# 16x16.net
KiCad netlist of a schematic drawn in EAGLE
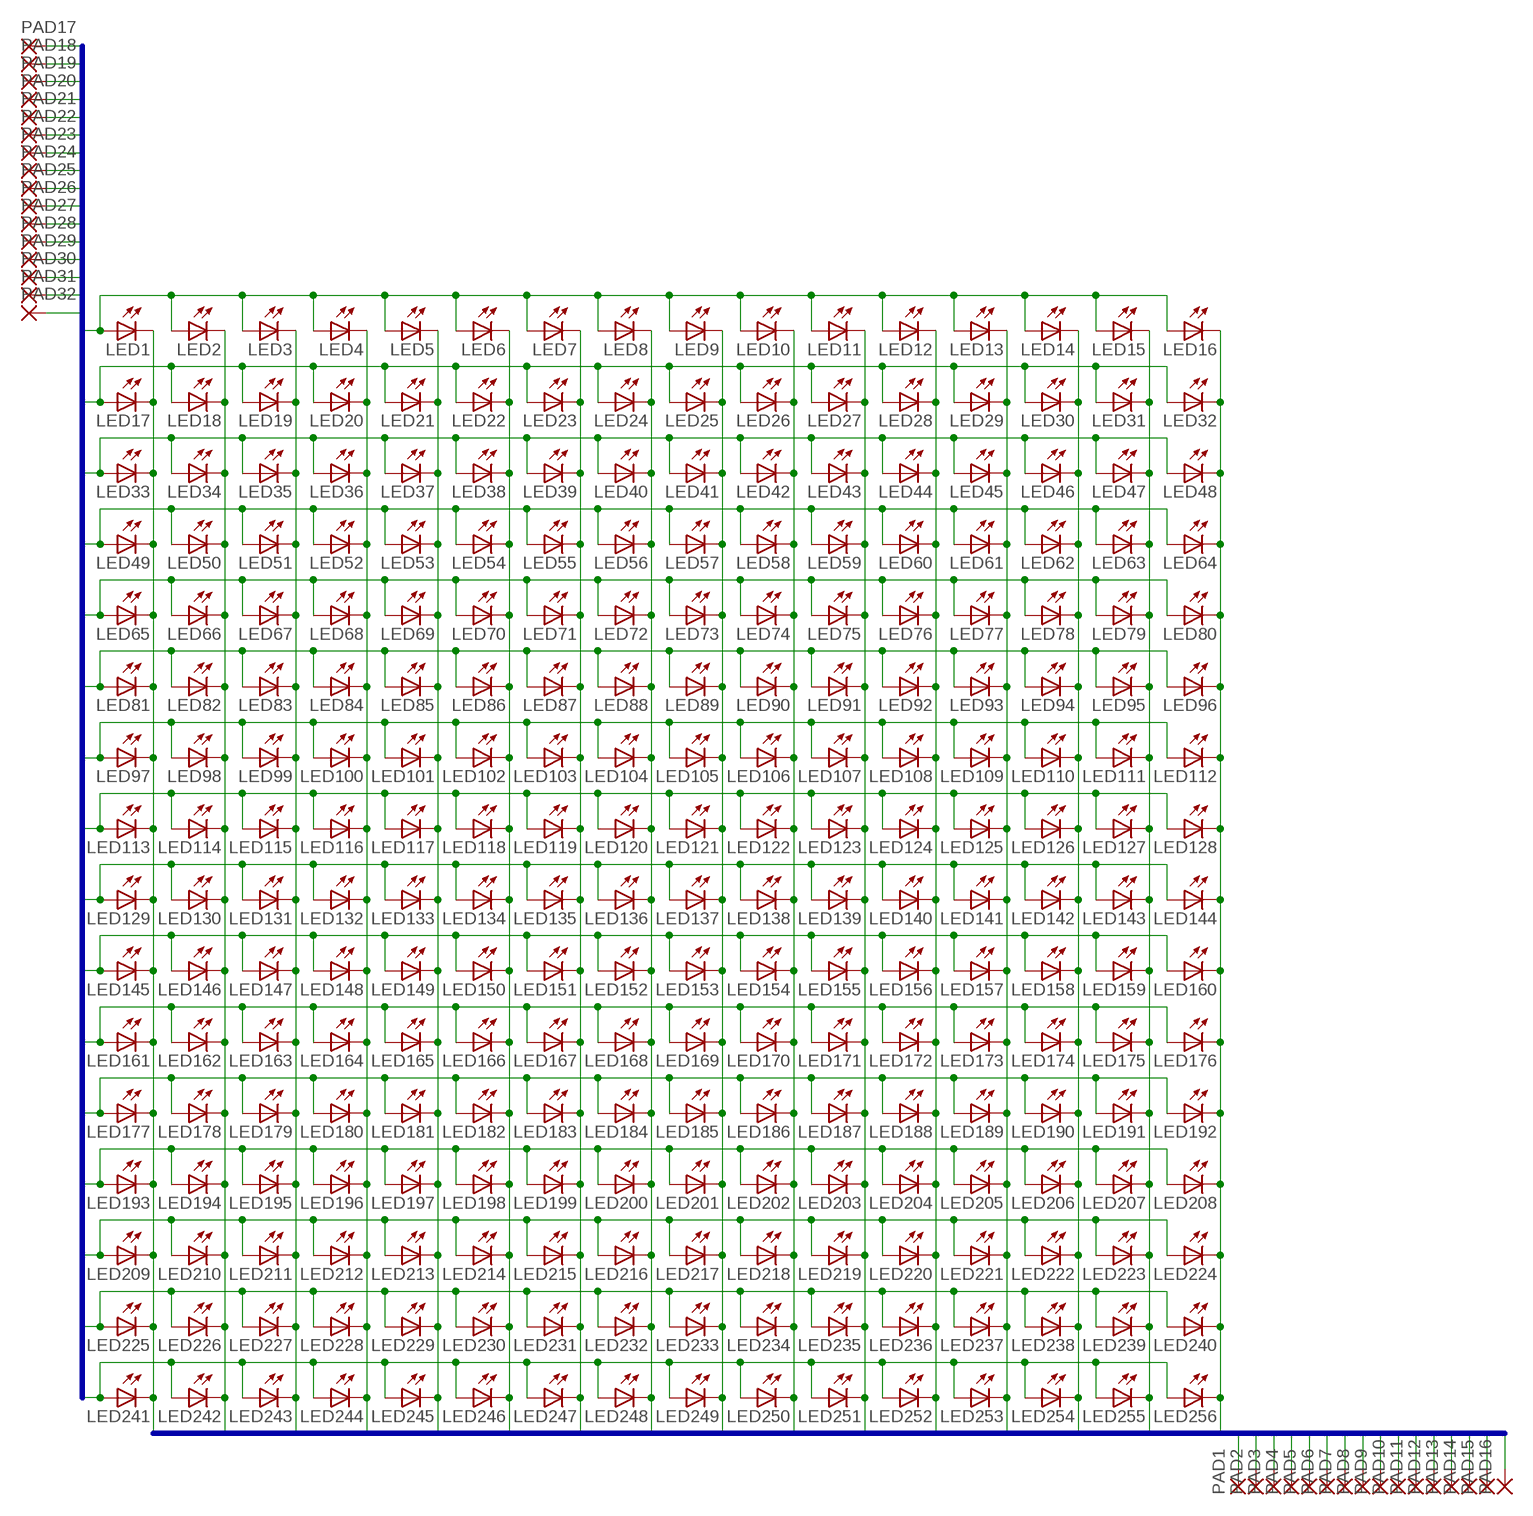
[diagram p0: schematic, sheet 1]

(export (version "E")
  (design (tool "Eeschema 10.0.6"))
  (components
    (comp (ref "LED1")
      (value "LEDSML0603")
      (footprint "eagle-import:SML0603")
      (libsource (lib "eagle-import") (part "LEDSML0603"))
    )
    (comp (ref "LED2")
      (value "LEDSML0603")
      (footprint "eagle-import:SML0603")
      (libsource (lib "eagle-import") (part "LEDSML0603"))
    )
    (comp (ref "LED3")
      (value "LEDSML0603")
      (footprint "eagle-import:SML0603")
      (libsource (lib "eagle-import") (part "LEDSML0603"))
    )
    (comp (ref "LED4")
      (value "LEDSML0603")
      (footprint "eagle-import:SML0603")
      (libsource (lib "eagle-import") (part "LEDSML0603"))
    )
    (comp (ref "LED5")
      (value "LEDSML0603")
      (footprint "eagle-import:SML0603")
      (libsource (lib "eagle-import") (part "LEDSML0603"))
    )
    (comp (ref "LED6")
      (value "LEDSML0603")
      (footprint "eagle-import:SML0603")
      (libsource (lib "eagle-import") (part "LEDSML0603"))
    )
    (comp (ref "LED7")
      (value "LEDSML0603")
      (footprint "eagle-import:SML0603")
      (libsource (lib "eagle-import") (part "LEDSML0603"))
    )
    (comp (ref "LED8")
      (value "LEDSML0603")
      (footprint "eagle-import:SML0603")
      (libsource (lib "eagle-import") (part "LEDSML0603"))
    )
    (comp (ref "LED9")
      (value "LEDSML0603")
      (footprint "eagle-import:SML0603")
      (libsource (lib "eagle-import") (part "LEDSML0603"))
    )
    (comp (ref "LED10")
      (value "LEDSML0603")
      (footprint "eagle-import:SML0603")
      (libsource (lib "eagle-import") (part "LEDSML0603"))
    )
    (comp (ref "LED11")
      (value "LEDSML0603")
      (footprint "eagle-import:SML0603")
      (libsource (lib "eagle-import") (part "LEDSML0603"))
    )
    (comp (ref "LED12")
      (value "LEDSML0603")
      (footprint "eagle-import:SML0603")
      (libsource (lib "eagle-import") (part "LEDSML0603"))
    )
    (comp (ref "LED13")
      (value "LEDSML0603")
      (footprint "eagle-import:SML0603")
      (libsource (lib "eagle-import") (part "LEDSML0603"))
    )
    (comp (ref "LED14")
      (value "LEDSML0603")
      (footprint "eagle-import:SML0603")
      (libsource (lib "eagle-import") (part "LEDSML0603"))
    )
    (comp (ref "LED15")
      (value "LEDSML0603")
      (footprint "eagle-import:SML0603")
      (libsource (lib "eagle-import") (part "LEDSML0603"))
    )
    (comp (ref "LED16")
      (value "LEDSML0603")
      (footprint "eagle-import:SML0603")
      (libsource (lib "eagle-import") (part "LEDSML0603"))
    )
    (comp (ref "LED17")
      (value "LEDSML0603")
      (footprint "eagle-import:SML0603")
      (libsource (lib "eagle-import") (part "LEDSML0603"))
    )
    (comp (ref "LED18")
      (value "LEDSML0603")
      (footprint "eagle-import:SML0603")
      (libsource (lib "eagle-import") (part "LEDSML0603"))
    )
    (comp (ref "LED19")
      (value "LEDSML0603")
      (footprint "eagle-import:SML0603")
      (libsource (lib "eagle-import") (part "LEDSML0603"))
    )
    (comp (ref "LED20")
      (value "LEDSML0603")
      (footprint "eagle-import:SML0603")
      (libsource (lib "eagle-import") (part "LEDSML0603"))
    )
    (comp (ref "LED21")
      (value "LEDSML0603")
      (footprint "eagle-import:SML0603")
      (libsource (lib "eagle-import") (part "LEDSML0603"))
    )
    (comp (ref "LED22")
      (value "LEDSML0603")
      (footprint "eagle-import:SML0603")
      (libsource (lib "eagle-import") (part "LEDSML0603"))
    )
    (comp (ref "LED23")
      (value "LEDSML0603")
      (footprint "eagle-import:SML0603")
      (libsource (lib "eagle-import") (part "LEDSML0603"))
    )
    (comp (ref "LED24")
      (value "LEDSML0603")
      (footprint "eagle-import:SML0603")
      (libsource (lib "eagle-import") (part "LEDSML0603"))
    )
    (comp (ref "LED25")
      (value "LEDSML0603")
      (footprint "eagle-import:SML0603")
      (libsource (lib "eagle-import") (part "LEDSML0603"))
    )
    (comp (ref "LED26")
      (value "LEDSML0603")
      (footprint "eagle-import:SML0603")
      (libsource (lib "eagle-import") (part "LEDSML0603"))
    )
    (comp (ref "LED27")
      (value "LEDSML0603")
      (footprint "eagle-import:SML0603")
      (libsource (lib "eagle-import") (part "LEDSML0603"))
    )
    (comp (ref "LED28")
      (value "LEDSML0603")
      (footprint "eagle-import:SML0603")
      (libsource (lib "eagle-import") (part "LEDSML0603"))
    )
    (comp (ref "LED29")
      (value "LEDSML0603")
      (footprint "eagle-import:SML0603")
      (libsource (lib "eagle-import") (part "LEDSML0603"))
    )
    (comp (ref "LED30")
      (value "LEDSML0603")
      (footprint "eagle-import:SML0603")
      (libsource (lib "eagle-import") (part "LEDSML0603"))
    )
    (comp (ref "LED31")
      (value "LEDSML0603")
      (footprint "eagle-import:SML0603")
      (libsource (lib "eagle-import") (part "LEDSML0603"))
    )
    (comp (ref "LED32")
      (value "LEDSML0603")
      (footprint "eagle-import:SML0603")
      (libsource (lib "eagle-import") (part "LEDSML0603"))
    )
    (comp (ref "LED33")
      (value "LEDSML0603")
      (footprint "eagle-import:SML0603")
      (libsource (lib "eagle-import") (part "LEDSML0603"))
    )
    (comp (ref "LED34")
      (value "LEDSML0603")
      (footprint "eagle-import:SML0603")
      (libsource (lib "eagle-import") (part "LEDSML0603"))
    )
    (comp (ref "LED35")
      (value "LEDSML0603")
      (footprint "eagle-import:SML0603")
      (libsource (lib "eagle-import") (part "LEDSML0603"))
    )
    (comp (ref "LED36")
      (value "LEDSML0603")
      (footprint "eagle-import:SML0603")
      (libsource (lib "eagle-import") (part "LEDSML0603"))
    )
    (comp (ref "LED37")
      (value "LEDSML0603")
      (footprint "eagle-import:SML0603")
      (libsource (lib "eagle-import") (part "LEDSML0603"))
    )
    (comp (ref "LED38")
      (value "LEDSML0603")
      (footprint "eagle-import:SML0603")
      (libsource (lib "eagle-import") (part "LEDSML0603"))
    )
    (comp (ref "LED39")
      (value "LEDSML0603")
      (footprint "eagle-import:SML0603")
      (libsource (lib "eagle-import") (part "LEDSML0603"))
    )
    (comp (ref "LED40")
      (value "LEDSML0603")
      (footprint "eagle-import:SML0603")
      (libsource (lib "eagle-import") (part "LEDSML0603"))
    )
    (comp (ref "LED41")
      (value "LEDSML0603")
      (footprint "eagle-import:SML0603")
      (libsource (lib "eagle-import") (part "LEDSML0603"))
    )
    (comp (ref "LED42")
      (value "LEDSML0603")
      (footprint "eagle-import:SML0603")
      (libsource (lib "eagle-import") (part "LEDSML0603"))
    )
    (comp (ref "LED43")
      (value "LEDSML0603")
      (footprint "eagle-import:SML0603")
      (libsource (lib "eagle-import") (part "LEDSML0603"))
    )
    (comp (ref "LED44")
      (value "LEDSML0603")
      (footprint "eagle-import:SML0603")
      (libsource (lib "eagle-import") (part "LEDSML0603"))
    )
    (comp (ref "LED45")
      (value "LEDSML0603")
      (footprint "eagle-import:SML0603")
      (libsource (lib "eagle-import") (part "LEDSML0603"))
    )
    (comp (ref "LED46")
      (value "LEDSML0603")
      (footprint "eagle-import:SML0603")
      (libsource (lib "eagle-import") (part "LEDSML0603"))
    )
    (comp (ref "LED47")
      (value "LEDSML0603")
      (footprint "eagle-import:SML0603")
      (libsource (lib "eagle-import") (part "LEDSML0603"))
    )
    (comp (ref "LED48")
      (value "LEDSML0603")
      (footprint "eagle-import:SML0603")
      (libsource (lib "eagle-import") (part "LEDSML0603"))
    )
    (comp (ref "LED49")
      (value "LEDSML0603")
      (footprint "eagle-import:SML0603")
      (libsource (lib "eagle-import") (part "LEDSML0603"))
    )
    (comp (ref "LED50")
      (value "LEDSML0603")
      (footprint "eagle-import:SML0603")
      (libsource (lib "eagle-import") (part "LEDSML0603"))
    )
    (comp (ref "LED51")
      (value "LEDSML0603")
      (footprint "eagle-import:SML0603")
      (libsource (lib "eagle-import") (part "LEDSML0603"))
    )
    (comp (ref "LED52")
      (value "LEDSML0603")
      (footprint "eagle-import:SML0603")
      (libsource (lib "eagle-import") (part "LEDSML0603"))
    )
    (comp (ref "LED53")
      (value "LEDSML0603")
      (footprint "eagle-import:SML0603")
      (libsource (lib "eagle-import") (part "LEDSML0603"))
    )
    (comp (ref "LED54")
      (value "LEDSML0603")
      (footprint "eagle-import:SML0603")
      (libsource (lib "eagle-import") (part "LEDSML0603"))
    )
    (comp (ref "LED55")
      (value "LEDSML0603")
      (footprint "eagle-import:SML0603")
      (libsource (lib "eagle-import") (part "LEDSML0603"))
    )
    (comp (ref "LED56")
      (value "LEDSML0603")
      (footprint "eagle-import:SML0603")
      (libsource (lib "eagle-import") (part "LEDSML0603"))
    )
    (comp (ref "LED57")
      (value "LEDSML0603")
      (footprint "eagle-import:SML0603")
      (libsource (lib "eagle-import") (part "LEDSML0603"))
    )
    (comp (ref "LED58")
      (value "LEDSML0603")
      (footprint "eagle-import:SML0603")
      (libsource (lib "eagle-import") (part "LEDSML0603"))
    )
    (comp (ref "LED59")
      (value "LEDSML0603")
      (footprint "eagle-import:SML0603")
      (libsource (lib "eagle-import") (part "LEDSML0603"))
    )
    (comp (ref "LED60")
      (value "LEDSML0603")
      (footprint "eagle-import:SML0603")
      (libsource (lib "eagle-import") (part "LEDSML0603"))
    )
    (comp (ref "LED61")
      (value "LEDSML0603")
      (footprint "eagle-import:SML0603")
      (libsource (lib "eagle-import") (part "LEDSML0603"))
    )
    (comp (ref "LED62")
      (value "LEDSML0603")
      (footprint "eagle-import:SML0603")
      (libsource (lib "eagle-import") (part "LEDSML0603"))
    )
    (comp (ref "LED63")
      (value "LEDSML0603")
      (footprint "eagle-import:SML0603")
      (libsource (lib "eagle-import") (part "LEDSML0603"))
    )
    (comp (ref "LED64")
      (value "LEDSML0603")
      (footprint "eagle-import:SML0603")
      (libsource (lib "eagle-import") (part "LEDSML0603"))
    )
    (comp (ref "LED65")
      (value "LEDSML0603")
      (footprint "eagle-import:SML0603")
      (libsource (lib "eagle-import") (part "LEDSML0603"))
    )
    (comp (ref "LED66")
      (value "LEDSML0603")
      (footprint "eagle-import:SML0603")
      (libsource (lib "eagle-import") (part "LEDSML0603"))
    )
    (comp (ref "LED67")
      (value "LEDSML0603")
      (footprint "eagle-import:SML0603")
      (libsource (lib "eagle-import") (part "LEDSML0603"))
    )
    (comp (ref "LED68")
      (value "LEDSML0603")
      (footprint "eagle-import:SML0603")
      (libsource (lib "eagle-import") (part "LEDSML0603"))
    )
    (comp (ref "LED69")
      (value "LEDSML0603")
      (footprint "eagle-import:SML0603")
      (libsource (lib "eagle-import") (part "LEDSML0603"))
    )
    (comp (ref "LED70")
      (value "LEDSML0603")
      (footprint "eagle-import:SML0603")
      (libsource (lib "eagle-import") (part "LEDSML0603"))
    )
    (comp (ref "LED71")
      (value "LEDSML0603")
      (footprint "eagle-import:SML0603")
      (libsource (lib "eagle-import") (part "LEDSML0603"))
    )
    (comp (ref "LED72")
      (value "LEDSML0603")
      (footprint "eagle-import:SML0603")
      (libsource (lib "eagle-import") (part "LEDSML0603"))
    )
    (comp (ref "LED73")
      (value "LEDSML0603")
      (footprint "eagle-import:SML0603")
      (libsource (lib "eagle-import") (part "LEDSML0603"))
    )
    (comp (ref "LED74")
      (value "LEDSML0603")
      (footprint "eagle-import:SML0603")
      (libsource (lib "eagle-import") (part "LEDSML0603"))
    )
    (comp (ref "LED75")
      (value "LEDSML0603")
      (footprint "eagle-import:SML0603")
      (libsource (lib "eagle-import") (part "LEDSML0603"))
    )
    (comp (ref "LED76")
      (value "LEDSML0603")
      (footprint "eagle-import:SML0603")
      (libsource (lib "eagle-import") (part "LEDSML0603"))
    )
    (comp (ref "LED77")
      (value "LEDSML0603")
      (footprint "eagle-import:SML0603")
      (libsource (lib "eagle-import") (part "LEDSML0603"))
    )
    (comp (ref "LED78")
      (value "LEDSML0603")
      (footprint "eagle-import:SML0603")
      (libsource (lib "eagle-import") (part "LEDSML0603"))
    )
    (comp (ref "LED79")
      (value "LEDSML0603")
      (footprint "eagle-import:SML0603")
      (libsource (lib "eagle-import") (part "LEDSML0603"))
    )
    (comp (ref "LED80")
      (value "LEDSML0603")
      (footprint "eagle-import:SML0603")
      (libsource (lib "eagle-import") (part "LEDSML0603"))
    )
    (comp (ref "LED81")
      (value "LEDSML0603")
      (footprint "eagle-import:SML0603")
      (libsource (lib "eagle-import") (part "LEDSML0603"))
    )
    (comp (ref "LED82")
      (value "LEDSML0603")
      (footprint "eagle-import:SML0603")
      (libsource (lib "eagle-import") (part "LEDSML0603"))
    )
    (comp (ref "LED83")
      (value "LEDSML0603")
      (footprint "eagle-import:SML0603")
      (libsource (lib "eagle-import") (part "LEDSML0603"))
    )
    (comp (ref "LED84")
      (value "LEDSML0603")
      (footprint "eagle-import:SML0603")
      (libsource (lib "eagle-import") (part "LEDSML0603"))
    )
    (comp (ref "LED85")
      (value "LEDSML0603")
      (footprint "eagle-import:SML0603")
      (libsource (lib "eagle-import") (part "LEDSML0603"))
    )
    (comp (ref "LED86")
      (value "LEDSML0603")
      (footprint "eagle-import:SML0603")
      (libsource (lib "eagle-import") (part "LEDSML0603"))
    )
    (comp (ref "LED87")
      (value "LEDSML0603")
      (footprint "eagle-import:SML0603")
      (libsource (lib "eagle-import") (part "LEDSML0603"))
    )
    (comp (ref "LED88")
      (value "LEDSML0603")
      (footprint "eagle-import:SML0603")
      (libsource (lib "eagle-import") (part "LEDSML0603"))
    )
    (comp (ref "LED89")
      (value "LEDSML0603")
      (footprint "eagle-import:SML0603")
      (libsource (lib "eagle-import") (part "LEDSML0603"))
    )
    (comp (ref "LED90")
      (value "LEDSML0603")
      (footprint "eagle-import:SML0603")
      (libsource (lib "eagle-import") (part "LEDSML0603"))
    )
    (comp (ref "LED91")
      (value "LEDSML0603")
      (footprint "eagle-import:SML0603")
      (libsource (lib "eagle-import") (part "LEDSML0603"))
    )
    (comp (ref "LED92")
      (value "LEDSML0603")
      (footprint "eagle-import:SML0603")
      (libsource (lib "eagle-import") (part "LEDSML0603"))
    )
    (comp (ref "LED93")
      (value "LEDSML0603")
      (footprint "eagle-import:SML0603")
      (libsource (lib "eagle-import") (part "LEDSML0603"))
    )
    (comp (ref "LED94")
      (value "LEDSML0603")
      (footprint "eagle-import:SML0603")
      (libsource (lib "eagle-import") (part "LEDSML0603"))
    )
    (comp (ref "LED95")
      (value "LEDSML0603")
      (footprint "eagle-import:SML0603")
      (libsource (lib "eagle-import") (part "LEDSML0603"))
    )
    (comp (ref "LED96")
      (value "LEDSML0603")
      (footprint "eagle-import:SML0603")
      (libsource (lib "eagle-import") (part "LEDSML0603"))
    )
    (comp (ref "LED97")
      (value "LEDSML0603")
      (footprint "eagle-import:SML0603")
      (libsource (lib "eagle-import") (part "LEDSML0603"))
    )
    (comp (ref "LED98")
      (value "LEDSML0603")
      (footprint "eagle-import:SML0603")
      (libsource (lib "eagle-import") (part "LEDSML0603"))
    )
    (comp (ref "LED99")
      (value "LEDSML0603")
      (footprint "eagle-import:SML0603")
      (libsource (lib "eagle-import") (part "LEDSML0603"))
    )
    (comp (ref "LED100")
      (value "LEDSML0603")
      (footprint "eagle-import:SML0603")
      (libsource (lib "eagle-import") (part "LEDSML0603"))
    )
    (comp (ref "LED101")
      (value "LEDSML0603")
      (footprint "eagle-import:SML0603")
      (libsource (lib "eagle-import") (part "LEDSML0603"))
    )
    (comp (ref "LED102")
      (value "LEDSML0603")
      (footprint "eagle-import:SML0603")
      (libsource (lib "eagle-import") (part "LEDSML0603"))
    )
    (comp (ref "LED103")
      (value "LEDSML0603")
      (footprint "eagle-import:SML0603")
      (libsource (lib "eagle-import") (part "LEDSML0603"))
    )
    (comp (ref "LED104")
      (value "LEDSML0603")
      (footprint "eagle-import:SML0603")
      (libsource (lib "eagle-import") (part "LEDSML0603"))
    )
    (comp (ref "LED105")
      (value "LEDSML0603")
      (footprint "eagle-import:SML0603")
      (libsource (lib "eagle-import") (part "LEDSML0603"))
    )
    (comp (ref "LED106")
      (value "LEDSML0603")
      (footprint "eagle-import:SML0603")
      (libsource (lib "eagle-import") (part "LEDSML0603"))
    )
    (comp (ref "LED107")
      (value "LEDSML0603")
      (footprint "eagle-import:SML0603")
      (libsource (lib "eagle-import") (part "LEDSML0603"))
    )
    (comp (ref "LED108")
      (value "LEDSML0603")
      (footprint "eagle-import:SML0603")
      (libsource (lib "eagle-import") (part "LEDSML0603"))
    )
    (comp (ref "LED109")
      (value "LEDSML0603")
      (footprint "eagle-import:SML0603")
      (libsource (lib "eagle-import") (part "LEDSML0603"))
    )
    (comp (ref "LED110")
      (value "LEDSML0603")
      (footprint "eagle-import:SML0603")
      (libsource (lib "eagle-import") (part "LEDSML0603"))
    )
    (comp (ref "LED111")
      (value "LEDSML0603")
      (footprint "eagle-import:SML0603")
      (libsource (lib "eagle-import") (part "LEDSML0603"))
    )
    (comp (ref "LED112")
      (value "LEDSML0603")
      (footprint "eagle-import:SML0603")
      (libsource (lib "eagle-import") (part "LEDSML0603"))
    )
    (comp (ref "LED113")
      (value "LEDSML0603")
      (footprint "eagle-import:SML0603")
      (libsource (lib "eagle-import") (part "LEDSML0603"))
    )
    (comp (ref "LED114")
      (value "LEDSML0603")
      (footprint "eagle-import:SML0603")
      (libsource (lib "eagle-import") (part "LEDSML0603"))
    )
    (comp (ref "LED115")
      (value "LEDSML0603")
      (footprint "eagle-import:SML0603")
      (libsource (lib "eagle-import") (part "LEDSML0603"))
    )
    (comp (ref "LED116")
      (value "LEDSML0603")
      (footprint "eagle-import:SML0603")
      (libsource (lib "eagle-import") (part "LEDSML0603"))
    )
    (comp (ref "LED117")
      (value "LEDSML0603")
      (footprint "eagle-import:SML0603")
      (libsource (lib "eagle-import") (part "LEDSML0603"))
    )
    (comp (ref "LED118")
      (value "LEDSML0603")
      (footprint "eagle-import:SML0603")
      (libsource (lib "eagle-import") (part "LEDSML0603"))
    )
    (comp (ref "LED119")
      (value "LEDSML0603")
      (footprint "eagle-import:SML0603")
      (libsource (lib "eagle-import") (part "LEDSML0603"))
    )
    (comp (ref "LED120")
      (value "LEDSML0603")
      (footprint "eagle-import:SML0603")
      (libsource (lib "eagle-import") (part "LEDSML0603"))
    )
    (comp (ref "LED121")
      (value "LEDSML0603")
      (footprint "eagle-import:SML0603")
      (libsource (lib "eagle-import") (part "LEDSML0603"))
    )
    (comp (ref "LED122")
      (value "LEDSML0603")
      (footprint "eagle-import:SML0603")
      (libsource (lib "eagle-import") (part "LEDSML0603"))
    )
    (comp (ref "LED123")
      (value "LEDSML0603")
      (footprint "eagle-import:SML0603")
      (libsource (lib "eagle-import") (part "LEDSML0603"))
    )
    (comp (ref "LED124")
      (value "LEDSML0603")
      (footprint "eagle-import:SML0603")
      (libsource (lib "eagle-import") (part "LEDSML0603"))
    )
    (comp (ref "LED125")
      (value "LEDSML0603")
      (footprint "eagle-import:SML0603")
      (libsource (lib "eagle-import") (part "LEDSML0603"))
    )
    (comp (ref "LED126")
      (value "LEDSML0603")
      (footprint "eagle-import:SML0603")
      (libsource (lib "eagle-import") (part "LEDSML0603"))
    )
    (comp (ref "LED127")
      (value "LEDSML0603")
      (footprint "eagle-import:SML0603")
      (libsource (lib "eagle-import") (part "LEDSML0603"))
    )
    (comp (ref "LED128")
      (value "LEDSML0603")
      (footprint "eagle-import:SML0603")
      (libsource (lib "eagle-import") (part "LEDSML0603"))
    )
    (comp (ref "LED129")
      (value "LEDSML0603")
      (footprint "eagle-import:SML0603")
      (libsource (lib "eagle-import") (part "LEDSML0603"))
    )
    (comp (ref "LED130")
      (value "LEDSML0603")
      (footprint "eagle-import:SML0603")
      (libsource (lib "eagle-import") (part "LEDSML0603"))
    )
    (comp (ref "LED131")
      (value "LEDSML0603")
      (footprint "eagle-import:SML0603")
      (libsource (lib "eagle-import") (part "LEDSML0603"))
    )
    (comp (ref "LED132")
      (value "LEDSML0603")
      (footprint "eagle-import:SML0603")
      (libsource (lib "eagle-import") (part "LEDSML0603"))
    )
    (comp (ref "LED133")
      (value "LEDSML0603")
      (footprint "eagle-import:SML0603")
      (libsource (lib "eagle-import") (part "LEDSML0603"))
    )
    (comp (ref "LED134")
      (value "LEDSML0603")
      (footprint "eagle-import:SML0603")
      (libsource (lib "eagle-import") (part "LEDSML0603"))
    )
    (comp (ref "LED135")
      (value "LEDSML0603")
      (footprint "eagle-import:SML0603")
      (libsource (lib "eagle-import") (part "LEDSML0603"))
    )
    (comp (ref "LED136")
      (value "LEDSML0603")
      (footprint "eagle-import:SML0603")
      (libsource (lib "eagle-import") (part "LEDSML0603"))
    )
    (comp (ref "LED137")
      (value "LEDSML0603")
      (footprint "eagle-import:SML0603")
      (libsource (lib "eagle-import") (part "LEDSML0603"))
    )
    (comp (ref "LED138")
      (value "LEDSML0603")
      (footprint "eagle-import:SML0603")
      (libsource (lib "eagle-import") (part "LEDSML0603"))
    )
    (comp (ref "LED139")
      (value "LEDSML0603")
      (footprint "eagle-import:SML0603")
      (libsource (lib "eagle-import") (part "LEDSML0603"))
    )
    (comp (ref "LED140")
      (value "LEDSML0603")
      (footprint "eagle-import:SML0603")
      (libsource (lib "eagle-import") (part "LEDSML0603"))
    )
    (comp (ref "LED141")
      (value "LEDSML0603")
      (footprint "eagle-import:SML0603")
      (libsource (lib "eagle-import") (part "LEDSML0603"))
    )
    (comp (ref "LED142")
      (value "LEDSML0603")
      (footprint "eagle-import:SML0603")
      (libsource (lib "eagle-import") (part "LEDSML0603"))
    )
    (comp (ref "LED143")
      (value "LEDSML0603")
      (footprint "eagle-import:SML0603")
      (libsource (lib "eagle-import") (part "LEDSML0603"))
    )
    (comp (ref "LED144")
      (value "LEDSML0603")
      (footprint "eagle-import:SML0603")
      (libsource (lib "eagle-import") (part "LEDSML0603"))
    )
    (comp (ref "LED145")
      (value "LEDSML0603")
      (footprint "eagle-import:SML0603")
      (libsource (lib "eagle-import") (part "LEDSML0603"))
    )
    (comp (ref "LED146")
      (value "LEDSML0603")
      (footprint "eagle-import:SML0603")
      (libsource (lib "eagle-import") (part "LEDSML0603"))
    )
    (comp (ref "LED147")
      (value "LEDSML0603")
      (footprint "eagle-import:SML0603")
      (libsource (lib "eagle-import") (part "LEDSML0603"))
    )
    (comp (ref "LED148")
      (value "LEDSML0603")
      (footprint "eagle-import:SML0603")
      (libsource (lib "eagle-import") (part "LEDSML0603"))
    )
    (comp (ref "LED149")
      (value "LEDSML0603")
      (footprint "eagle-import:SML0603")
      (libsource (lib "eagle-import") (part "LEDSML0603"))
    )
    (comp (ref "LED150")
      (value "LEDSML0603")
      (footprint "eagle-import:SML0603")
      (libsource (lib "eagle-import") (part "LEDSML0603"))
    )
    (comp (ref "LED151")
      (value "LEDSML0603")
      (footprint "eagle-import:SML0603")
      (libsource (lib "eagle-import") (part "LEDSML0603"))
    )
    (comp (ref "LED152")
      (value "LEDSML0603")
      (footprint "eagle-import:SML0603")
      (libsource (lib "eagle-import") (part "LEDSML0603"))
    )
    (comp (ref "LED153")
      (value "LEDSML0603")
      (footprint "eagle-import:SML0603")
      (libsource (lib "eagle-import") (part "LEDSML0603"))
    )
    (comp (ref "LED154")
      (value "LEDSML0603")
      (footprint "eagle-import:SML0603")
      (libsource (lib "eagle-import") (part "LEDSML0603"))
    )
    (comp (ref "LED155")
      (value "LEDSML0603")
      (footprint "eagle-import:SML0603")
      (libsource (lib "eagle-import") (part "LEDSML0603"))
    )
    (comp (ref "LED156")
      (value "LEDSML0603")
      (footprint "eagle-import:SML0603")
      (libsource (lib "eagle-import") (part "LEDSML0603"))
    )
    (comp (ref "LED157")
      (value "LEDSML0603")
      (footprint "eagle-import:SML0603")
      (libsource (lib "eagle-import") (part "LEDSML0603"))
    )
    (comp (ref "LED158")
      (value "LEDSML0603")
      (footprint "eagle-import:SML0603")
      (libsource (lib "eagle-import") (part "LEDSML0603"))
    )
    (comp (ref "LED159")
      (value "LEDSML0603")
      (footprint "eagle-import:SML0603")
      (libsource (lib "eagle-import") (part "LEDSML0603"))
    )
    (comp (ref "LED160")
      (value "LEDSML0603")
      (footprint "eagle-import:SML0603")
      (libsource (lib "eagle-import") (part "LEDSML0603"))
    )
    (comp (ref "LED161")
      (value "LEDSML0603")
      (footprint "eagle-import:SML0603")
      (libsource (lib "eagle-import") (part "LEDSML0603"))
    )
    (comp (ref "LED162")
      (value "LEDSML0603")
      (footprint "eagle-import:SML0603")
      (libsource (lib "eagle-import") (part "LEDSML0603"))
    )
    (comp (ref "LED163")
      (value "LEDSML0603")
      (footprint "eagle-import:SML0603")
      (libsource (lib "eagle-import") (part "LEDSML0603"))
    )
    (comp (ref "LED164")
      (value "LEDSML0603")
      (footprint "eagle-import:SML0603")
      (libsource (lib "eagle-import") (part "LEDSML0603"))
    )
    (comp (ref "LED165")
      (value "LEDSML0603")
      (footprint "eagle-import:SML0603")
      (libsource (lib "eagle-import") (part "LEDSML0603"))
    )
    (comp (ref "LED166")
      (value "LEDSML0603")
      (footprint "eagle-import:SML0603")
      (libsource (lib "eagle-import") (part "LEDSML0603"))
    )
    (comp (ref "LED167")
      (value "LEDSML0603")
      (footprint "eagle-import:SML0603")
      (libsource (lib "eagle-import") (part "LEDSML0603"))
    )
    (comp (ref "LED168")
      (value "LEDSML0603")
      (footprint "eagle-import:SML0603")
      (libsource (lib "eagle-import") (part "LEDSML0603"))
    )
    (comp (ref "LED169")
      (value "LEDSML0603")
      (footprint "eagle-import:SML0603")
      (libsource (lib "eagle-import") (part "LEDSML0603"))
    )
    (comp (ref "LED170")
      (value "LEDSML0603")
      (footprint "eagle-import:SML0603")
      (libsource (lib "eagle-import") (part "LEDSML0603"))
    )
    (comp (ref "LED171")
      (value "LEDSML0603")
      (footprint "eagle-import:SML0603")
      (libsource (lib "eagle-import") (part "LEDSML0603"))
    )
    (comp (ref "LED172")
      (value "LEDSML0603")
      (footprint "eagle-import:SML0603")
      (libsource (lib "eagle-import") (part "LEDSML0603"))
    )
    (comp (ref "LED173")
      (value "LEDSML0603")
      (footprint "eagle-import:SML0603")
      (libsource (lib "eagle-import") (part "LEDSML0603"))
    )
    (comp (ref "LED174")
      (value "LEDSML0603")
      (footprint "eagle-import:SML0603")
      (libsource (lib "eagle-import") (part "LEDSML0603"))
    )
    (comp (ref "LED175")
      (value "LEDSML0603")
      (footprint "eagle-import:SML0603")
      (libsource (lib "eagle-import") (part "LEDSML0603"))
    )
    (comp (ref "LED176")
      (value "LEDSML0603")
      (footprint "eagle-import:SML0603")
      (libsource (lib "eagle-import") (part "LEDSML0603"))
    )
    (comp (ref "LED177")
      (value "LEDSML0603")
      (footprint "eagle-import:SML0603")
      (libsource (lib "eagle-import") (part "LEDSML0603"))
    )
    (comp (ref "LED178")
      (value "LEDSML0603")
      (footprint "eagle-import:SML0603")
      (libsource (lib "eagle-import") (part "LEDSML0603"))
    )
    (comp (ref "LED179")
      (value "LEDSML0603")
      (footprint "eagle-import:SML0603")
      (libsource (lib "eagle-import") (part "LEDSML0603"))
    )
    (comp (ref "LED180")
      (value "LEDSML0603")
      (footprint "eagle-import:SML0603")
      (libsource (lib "eagle-import") (part "LEDSML0603"))
    )
    (comp (ref "LED181")
      (value "LEDSML0603")
      (footprint "eagle-import:SML0603")
      (libsource (lib "eagle-import") (part "LEDSML0603"))
    )
    (comp (ref "LED182")
      (value "LEDSML0603")
      (footprint "eagle-import:SML0603")
      (libsource (lib "eagle-import") (part "LEDSML0603"))
    )
    (comp (ref "LED183")
      (value "LEDSML0603")
      (footprint "eagle-import:SML0603")
      (libsource (lib "eagle-import") (part "LEDSML0603"))
    )
    (comp (ref "LED184")
      (value "LEDSML0603")
      (footprint "eagle-import:SML0603")
      (libsource (lib "eagle-import") (part "LEDSML0603"))
    )
    (comp (ref "LED185")
      (value "LEDSML0603")
      (footprint "eagle-import:SML0603")
      (libsource (lib "eagle-import") (part "LEDSML0603"))
    )
    (comp (ref "LED186")
      (value "LEDSML0603")
      (footprint "eagle-import:SML0603")
      (libsource (lib "eagle-import") (part "LEDSML0603"))
    )
    (comp (ref "LED187")
      (value "LEDSML0603")
      (footprint "eagle-import:SML0603")
      (libsource (lib "eagle-import") (part "LEDSML0603"))
    )
    (comp (ref "LED188")
      (value "LEDSML0603")
      (footprint "eagle-import:SML0603")
      (libsource (lib "eagle-import") (part "LEDSML0603"))
    )
    (comp (ref "LED189")
      (value "LEDSML0603")
      (footprint "eagle-import:SML0603")
      (libsource (lib "eagle-import") (part "LEDSML0603"))
    )
    (comp (ref "LED190")
      (value "LEDSML0603")
      (footprint "eagle-import:SML0603")
      (libsource (lib "eagle-import") (part "LEDSML0603"))
    )
    (comp (ref "LED191")
      (value "LEDSML0603")
      (footprint "eagle-import:SML0603")
      (libsource (lib "eagle-import") (part "LEDSML0603"))
    )
    (comp (ref "LED192")
      (value "LEDSML0603")
      (footprint "eagle-import:SML0603")
      (libsource (lib "eagle-import") (part "LEDSML0603"))
    )
    (comp (ref "LED193")
      (value "LEDSML0603")
      (footprint "eagle-import:SML0603")
      (libsource (lib "eagle-import") (part "LEDSML0603"))
    )
    (comp (ref "LED194")
      (value "LEDSML0603")
      (footprint "eagle-import:SML0603")
      (libsource (lib "eagle-import") (part "LEDSML0603"))
    )
    (comp (ref "LED195")
      (value "LEDSML0603")
      (footprint "eagle-import:SML0603")
      (libsource (lib "eagle-import") (part "LEDSML0603"))
    )
    (comp (ref "LED196")
      (value "LEDSML0603")
      (footprint "eagle-import:SML0603")
      (libsource (lib "eagle-import") (part "LEDSML0603"))
    )
    (comp (ref "LED197")
      (value "LEDSML0603")
      (footprint "eagle-import:SML0603")
      (libsource (lib "eagle-import") (part "LEDSML0603"))
    )
    (comp (ref "LED198")
      (value "LEDSML0603")
      (footprint "eagle-import:SML0603")
      (libsource (lib "eagle-import") (part "LEDSML0603"))
    )
    (comp (ref "LED199")
      (value "LEDSML0603")
      (footprint "eagle-import:SML0603")
      (libsource (lib "eagle-import") (part "LEDSML0603"))
    )
    (comp (ref "LED200")
      (value "LEDSML0603")
      (footprint "eagle-import:SML0603")
      (libsource (lib "eagle-import") (part "LEDSML0603"))
    )
    (comp (ref "LED201")
      (value "LEDSML0603")
      (footprint "eagle-import:SML0603")
      (libsource (lib "eagle-import") (part "LEDSML0603"))
    )
    (comp (ref "LED202")
      (value "LEDSML0603")
      (footprint "eagle-import:SML0603")
      (libsource (lib "eagle-import") (part "LEDSML0603"))
    )
    (comp (ref "LED203")
      (value "LEDSML0603")
      (footprint "eagle-import:SML0603")
      (libsource (lib "eagle-import") (part "LEDSML0603"))
    )
    (comp (ref "LED204")
      (value "LEDSML0603")
      (footprint "eagle-import:SML0603")
      (libsource (lib "eagle-import") (part "LEDSML0603"))
    )
    (comp (ref "LED205")
      (value "LEDSML0603")
      (footprint "eagle-import:SML0603")
      (libsource (lib "eagle-import") (part "LEDSML0603"))
    )
    (comp (ref "LED206")
      (value "LEDSML0603")
      (footprint "eagle-import:SML0603")
      (libsource (lib "eagle-import") (part "LEDSML0603"))
    )
    (comp (ref "LED207")
      (value "LEDSML0603")
      (footprint "eagle-import:SML0603")
      (libsource (lib "eagle-import") (part "LEDSML0603"))
    )
    (comp (ref "LED208")
      (value "LEDSML0603")
      (footprint "eagle-import:SML0603")
      (libsource (lib "eagle-import") (part "LEDSML0603"))
    )
    (comp (ref "LED209")
      (value "LEDSML0603")
      (footprint "eagle-import:SML0603")
      (libsource (lib "eagle-import") (part "LEDSML0603"))
    )
    (comp (ref "LED210")
      (value "LEDSML0603")
      (footprint "eagle-import:SML0603")
      (libsource (lib "eagle-import") (part "LEDSML0603"))
    )
    (comp (ref "LED211")
      (value "LEDSML0603")
      (footprint "eagle-import:SML0603")
      (libsource (lib "eagle-import") (part "LEDSML0603"))
    )
    (comp (ref "LED212")
      (value "LEDSML0603")
      (footprint "eagle-import:SML0603")
      (libsource (lib "eagle-import") (part "LEDSML0603"))
    )
    (comp (ref "LED213")
      (value "LEDSML0603")
      (footprint "eagle-import:SML0603")
      (libsource (lib "eagle-import") (part "LEDSML0603"))
    )
    (comp (ref "LED214")
      (value "LEDSML0603")
      (footprint "eagle-import:SML0603")
      (libsource (lib "eagle-import") (part "LEDSML0603"))
    )
    (comp (ref "LED215")
      (value "LEDSML0603")
      (footprint "eagle-import:SML0603")
      (libsource (lib "eagle-import") (part "LEDSML0603"))
    )
    (comp (ref "LED216")
      (value "LEDSML0603")
      (footprint "eagle-import:SML0603")
      (libsource (lib "eagle-import") (part "LEDSML0603"))
    )
    (comp (ref "LED217")
      (value "LEDSML0603")
      (footprint "eagle-import:SML0603")
      (libsource (lib "eagle-import") (part "LEDSML0603"))
    )
    (comp (ref "LED218")
      (value "LEDSML0603")
      (footprint "eagle-import:SML0603")
      (libsource (lib "eagle-import") (part "LEDSML0603"))
    )
    (comp (ref "LED219")
      (value "LEDSML0603")
      (footprint "eagle-import:SML0603")
      (libsource (lib "eagle-import") (part "LEDSML0603"))
    )
    (comp (ref "LED220")
      (value "LEDSML0603")
      (footprint "eagle-import:SML0603")
      (libsource (lib "eagle-import") (part "LEDSML0603"))
    )
    (comp (ref "LED221")
      (value "LEDSML0603")
      (footprint "eagle-import:SML0603")
      (libsource (lib "eagle-import") (part "LEDSML0603"))
    )
    (comp (ref "LED222")
      (value "LEDSML0603")
      (footprint "eagle-import:SML0603")
      (libsource (lib "eagle-import") (part "LEDSML0603"))
    )
    (comp (ref "LED223")
      (value "LEDSML0603")
      (footprint "eagle-import:SML0603")
      (libsource (lib "eagle-import") (part "LEDSML0603"))
    )
    (comp (ref "LED224")
      (value "LEDSML0603")
      (footprint "eagle-import:SML0603")
      (libsource (lib "eagle-import") (part "LEDSML0603"))
    )
    (comp (ref "LED225")
      (value "LEDSML0603")
      (footprint "eagle-import:SML0603")
      (libsource (lib "eagle-import") (part "LEDSML0603"))
    )
    (comp (ref "LED226")
      (value "LEDSML0603")
      (footprint "eagle-import:SML0603")
      (libsource (lib "eagle-import") (part "LEDSML0603"))
    )
    (comp (ref "LED227")
      (value "LEDSML0603")
      (footprint "eagle-import:SML0603")
      (libsource (lib "eagle-import") (part "LEDSML0603"))
    )
    (comp (ref "LED228")
      (value "LEDSML0603")
      (footprint "eagle-import:SML0603")
      (libsource (lib "eagle-import") (part "LEDSML0603"))
    )
    (comp (ref "LED229")
      (value "LEDSML0603")
      (footprint "eagle-import:SML0603")
      (libsource (lib "eagle-import") (part "LEDSML0603"))
    )
    (comp (ref "LED230")
      (value "LEDSML0603")
      (footprint "eagle-import:SML0603")
      (libsource (lib "eagle-import") (part "LEDSML0603"))
    )
    (comp (ref "LED231")
      (value "LEDSML0603")
      (footprint "eagle-import:SML0603")
      (libsource (lib "eagle-import") (part "LEDSML0603"))
    )
    (comp (ref "LED232")
      (value "LEDSML0603")
      (footprint "eagle-import:SML0603")
      (libsource (lib "eagle-import") (part "LEDSML0603"))
    )
    (comp (ref "LED233")
      (value "LEDSML0603")
      (footprint "eagle-import:SML0603")
      (libsource (lib "eagle-import") (part "LEDSML0603"))
    )
    (comp (ref "LED234")
      (value "LEDSML0603")
      (footprint "eagle-import:SML0603")
      (libsource (lib "eagle-import") (part "LEDSML0603"))
    )
    (comp (ref "LED235")
      (value "LEDSML0603")
      (footprint "eagle-import:SML0603")
      (libsource (lib "eagle-import") (part "LEDSML0603"))
    )
    (comp (ref "LED236")
      (value "LEDSML0603")
      (footprint "eagle-import:SML0603")
      (libsource (lib "eagle-import") (part "LEDSML0603"))
    )
    (comp (ref "LED237")
      (value "LEDSML0603")
      (footprint "eagle-import:SML0603")
      (libsource (lib "eagle-import") (part "LEDSML0603"))
    )
    (comp (ref "LED238")
      (value "LEDSML0603")
      (footprint "eagle-import:SML0603")
      (libsource (lib "eagle-import") (part "LEDSML0603"))
    )
    (comp (ref "LED239")
      (value "LEDSML0603")
      (footprint "eagle-import:SML0603")
      (libsource (lib "eagle-import") (part "LEDSML0603"))
    )
    (comp (ref "LED240")
      (value "LEDSML0603")
      (footprint "eagle-import:SML0603")
      (libsource (lib "eagle-import") (part "LEDSML0603"))
    )
    (comp (ref "LED241")
      (value "LEDSML0603")
      (footprint "eagle-import:SML0603")
      (libsource (lib "eagle-import") (part "LEDSML0603"))
    )
    (comp (ref "LED242")
      (value "LEDSML0603")
      (footprint "eagle-import:SML0603")
      (libsource (lib "eagle-import") (part "LEDSML0603"))
    )
    (comp (ref "LED243")
      (value "LEDSML0603")
      (footprint "eagle-import:SML0603")
      (libsource (lib "eagle-import") (part "LEDSML0603"))
    )
    (comp (ref "LED244")
      (value "LEDSML0603")
      (footprint "eagle-import:SML0603")
      (libsource (lib "eagle-import") (part "LEDSML0603"))
    )
    (comp (ref "LED245")
      (value "LEDSML0603")
      (footprint "eagle-import:SML0603")
      (libsource (lib "eagle-import") (part "LEDSML0603"))
    )
    (comp (ref "LED246")
      (value "LEDSML0603")
      (footprint "eagle-import:SML0603")
      (libsource (lib "eagle-import") (part "LEDSML0603"))
    )
    (comp (ref "LED247")
      (value "LEDSML0603")
      (footprint "eagle-import:SML0603")
      (libsource (lib "eagle-import") (part "LEDSML0603"))
    )
    (comp (ref "LED248")
      (value "LEDSML0603")
      (footprint "eagle-import:SML0603")
      (libsource (lib "eagle-import") (part "LEDSML0603"))
    )
    (comp (ref "LED249")
      (value "LEDSML0603")
      (footprint "eagle-import:SML0603")
      (libsource (lib "eagle-import") (part "LEDSML0603"))
    )
    (comp (ref "LED250")
      (value "LEDSML0603")
      (footprint "eagle-import:SML0603")
      (libsource (lib "eagle-import") (part "LEDSML0603"))
    )
    (comp (ref "LED251")
      (value "LEDSML0603")
      (footprint "eagle-import:SML0603")
      (libsource (lib "eagle-import") (part "LEDSML0603"))
    )
    (comp (ref "LED252")
      (value "LEDSML0603")
      (footprint "eagle-import:SML0603")
      (libsource (lib "eagle-import") (part "LEDSML0603"))
    )
    (comp (ref "LED253")
      (value "LEDSML0603")
      (footprint "eagle-import:SML0603")
      (libsource (lib "eagle-import") (part "LEDSML0603"))
    )
    (comp (ref "LED254")
      (value "LEDSML0603")
      (footprint "eagle-import:SML0603")
      (libsource (lib "eagle-import") (part "LEDSML0603"))
    )
    (comp (ref "LED255")
      (value "LEDSML0603")
      (footprint "eagle-import:SML0603")
      (libsource (lib "eagle-import") (part "LEDSML0603"))
    )
    (comp (ref "LED256")
      (value "LEDSML0603")
      (footprint "eagle-import:SML0603")
      (libsource (lib "eagle-import") (part "LEDSML0603"))
    )
    (comp (ref "PAD1")
      (value "SMD2")
      (footprint "eagle-import:SMD1,27-2,54")
      (libsource (lib "eagle-import") (part "SMD2"))
    )
    (comp (ref "PAD2")
      (value "SMD2")
      (footprint "eagle-import:SMD1,27-2,54")
      (libsource (lib "eagle-import") (part "SMD2"))
    )
    (comp (ref "PAD3")
      (value "SMD2")
      (footprint "eagle-import:SMD1,27-2,54")
      (libsource (lib "eagle-import") (part "SMD2"))
    )
    (comp (ref "PAD4")
      (value "SMD2")
      (footprint "eagle-import:SMD1,27-2,54")
      (libsource (lib "eagle-import") (part "SMD2"))
    )
    (comp (ref "PAD5")
      (value "SMD2")
      (footprint "eagle-import:SMD1,27-2,54")
      (libsource (lib "eagle-import") (part "SMD2"))
    )
    (comp (ref "PAD6")
      (value "SMD2")
      (footprint "eagle-import:SMD1,27-2,54")
      (libsource (lib "eagle-import") (part "SMD2"))
    )
    (comp (ref "PAD7")
      (value "SMD2")
      (footprint "eagle-import:SMD1,27-2,54")
      (libsource (lib "eagle-import") (part "SMD2"))
    )
    (comp (ref "PAD8")
      (value "SMD2")
      (footprint "eagle-import:SMD1,27-2,54")
      (libsource (lib "eagle-import") (part "SMD2"))
    )
    (comp (ref "PAD9")
      (value "SMD2")
      (footprint "eagle-import:SMD1,27-2,54")
      (libsource (lib "eagle-import") (part "SMD2"))
    )
    (comp (ref "PAD10")
      (value "SMD2")
      (footprint "eagle-import:SMD1,27-2,54")
      (libsource (lib "eagle-import") (part "SMD2"))
    )
    (comp (ref "PAD11")
      (value "SMD2")
      (footprint "eagle-import:SMD1,27-2,54")
      (libsource (lib "eagle-import") (part "SMD2"))
    )
    (comp (ref "PAD12")
      (value "SMD2")
      (footprint "eagle-import:SMD1,27-2,54")
      (libsource (lib "eagle-import") (part "SMD2"))
    )
    (comp (ref "PAD13")
      (value "SMD2")
      (footprint "eagle-import:SMD1,27-2,54")
      (libsource (lib "eagle-import") (part "SMD2"))
    )
    (comp (ref "PAD14")
      (value "SMD2")
      (footprint "eagle-import:SMD1,27-2,54")
      (libsource (lib "eagle-import") (part "SMD2"))
    )
    (comp (ref "PAD15")
      (value "SMD2")
      (footprint "eagle-import:SMD1,27-2,54")
      (libsource (lib "eagle-import") (part "SMD2"))
    )
    (comp (ref "PAD16")
      (value "SMD2")
      (footprint "eagle-import:SMD1,27-2,54")
      (libsource (lib "eagle-import") (part "SMD2"))
    )
    (comp (ref "PAD17")
      (value "SMD2")
      (footprint "eagle-import:SMD1,27-2,54")
      (libsource (lib "eagle-import") (part "SMD2"))
    )
    (comp (ref "PAD18")
      (value "SMD2")
      (footprint "eagle-import:SMD1,27-2,54")
      (libsource (lib "eagle-import") (part "SMD2"))
    )
    (comp (ref "PAD19")
      (value "SMD2")
      (footprint "eagle-import:SMD1,27-2,54")
      (libsource (lib "eagle-import") (part "SMD2"))
    )
    (comp (ref "PAD20")
      (value "SMD2")
      (footprint "eagle-import:SMD1,27-2,54")
      (libsource (lib "eagle-import") (part "SMD2"))
    )
    (comp (ref "PAD21")
      (value "SMD2")
      (footprint "eagle-import:SMD1,27-2,54")
      (libsource (lib "eagle-import") (part "SMD2"))
    )
    (comp (ref "PAD22")
      (value "SMD2")
      (footprint "eagle-import:SMD1,27-2,54")
      (libsource (lib "eagle-import") (part "SMD2"))
    )
    (comp (ref "PAD23")
      (value "SMD2")
      (footprint "eagle-import:SMD1,27-2,54")
      (libsource (lib "eagle-import") (part "SMD2"))
    )
    (comp (ref "PAD24")
      (value "SMD2")
      (footprint "eagle-import:SMD1,27-2,54")
      (libsource (lib "eagle-import") (part "SMD2"))
    )
    (comp (ref "PAD25")
      (value "SMD2")
      (footprint "eagle-import:SMD1,27-2,54")
      (libsource (lib "eagle-import") (part "SMD2"))
    )
    (comp (ref "PAD26")
      (value "SMD2")
      (footprint "eagle-import:SMD1,27-2,54")
      (libsource (lib "eagle-import") (part "SMD2"))
    )
    (comp (ref "PAD27")
      (value "SMD2")
      (footprint "eagle-import:SMD1,27-2,54")
      (libsource (lib "eagle-import") (part "SMD2"))
    )
    (comp (ref "PAD28")
      (value "SMD2")
      (footprint "eagle-import:SMD1,27-2,54")
      (libsource (lib "eagle-import") (part "SMD2"))
    )
    (comp (ref "PAD29")
      (value "SMD2")
      (footprint "eagle-import:SMD1,27-2,54")
      (libsource (lib "eagle-import") (part "SMD2"))
    )
    (comp (ref "PAD30")
      (value "SMD2")
      (footprint "eagle-import:SMD1,27-2,54")
      (libsource (lib "eagle-import") (part "SMD2"))
    )
    (comp (ref "PAD31")
      (value "SMD2")
      (footprint "eagle-import:SMD1,27-2,54")
      (libsource (lib "eagle-import") (part "SMD2"))
    )
    (comp (ref "PAD32")
      (value "SMD2")
      (footprint "eagle-import:SMD1,27-2,54")
      (libsource (lib "eagle-import") (part "SMD2"))
    )
  )
  (nets
    (net (code "1") (name "/X0") (class "Default")
      (node (ref "LED1") (pin "C") (pinfunction "C_C") (pintype "passive"))
      (node (ref "LED113") (pin "C") (pinfunction "C_C") (pintype "passive"))
      (node (ref "LED129") (pin "C") (pinfunction "C_C") (pintype "passive"))
      (node (ref "LED145") (pin "C") (pinfunction "C_C") (pintype "passive"))
      (node (ref "LED161") (pin "C") (pinfunction "C_C") (pintype "passive"))
      (node (ref "LED17") (pin "C") (pinfunction "C_C") (pintype "passive"))
      (node (ref "LED177") (pin "C") (pinfunction "C_C") (pintype "passive"))
      (node (ref "LED193") (pin "C") (pinfunction "C_C") (pintype "passive"))
      (node (ref "LED209") (pin "C") (pinfunction "C_C") (pintype "passive"))
      (node (ref "LED225") (pin "C") (pinfunction "C_C") (pintype "passive"))
      (node (ref "LED241") (pin "C") (pinfunction "C_C") (pintype "passive"))
      (node (ref "LED33") (pin "C") (pinfunction "C_C") (pintype "passive"))
      (node (ref "LED49") (pin "C") (pinfunction "C_C") (pintype "passive"))
      (node (ref "LED65") (pin "C") (pinfunction "C_C") (pintype "passive"))
      (node (ref "LED81") (pin "C") (pinfunction "C_C") (pintype "passive"))
      (node (ref "LED97") (pin "C") (pinfunction "C_C") (pintype "passive"))
      (node (ref "PAD1") (pin "1") (pinfunction "P_1") (pintype "passive"))
    )
    (net (code "2") (name "/X1") (class "Default")
      (node (ref "LED114") (pin "C") (pinfunction "C_C") (pintype "passive"))
      (node (ref "LED130") (pin "C") (pinfunction "C_C") (pintype "passive"))
      (node (ref "LED146") (pin "C") (pinfunction "C_C") (pintype "passive"))
      (node (ref "LED162") (pin "C") (pinfunction "C_C") (pintype "passive"))
      (node (ref "LED178") (pin "C") (pinfunction "C_C") (pintype "passive"))
      (node (ref "LED18") (pin "C") (pinfunction "C_C") (pintype "passive"))
      (node (ref "LED194") (pin "C") (pinfunction "C_C") (pintype "passive"))
      (node (ref "LED2") (pin "C") (pinfunction "C_C") (pintype "passive"))
      (node (ref "LED210") (pin "C") (pinfunction "C_C") (pintype "passive"))
      (node (ref "LED226") (pin "C") (pinfunction "C_C") (pintype "passive"))
      (node (ref "LED242") (pin "C") (pinfunction "C_C") (pintype "passive"))
      (node (ref "LED34") (pin "C") (pinfunction "C_C") (pintype "passive"))
      (node (ref "LED50") (pin "C") (pinfunction "C_C") (pintype "passive"))
      (node (ref "LED66") (pin "C") (pinfunction "C_C") (pintype "passive"))
      (node (ref "LED82") (pin "C") (pinfunction "C_C") (pintype "passive"))
      (node (ref "LED98") (pin "C") (pinfunction "C_C") (pintype "passive"))
      (node (ref "PAD2") (pin "1") (pinfunction "P_1") (pintype "passive"))
    )
    (net (code "3") (name "/X2") (class "Default")
      (node (ref "LED115") (pin "C") (pinfunction "C_C") (pintype "passive"))
      (node (ref "LED131") (pin "C") (pinfunction "C_C") (pintype "passive"))
      (node (ref "LED147") (pin "C") (pinfunction "C_C") (pintype "passive"))
      (node (ref "LED163") (pin "C") (pinfunction "C_C") (pintype "passive"))
      (node (ref "LED179") (pin "C") (pinfunction "C_C") (pintype "passive"))
      (node (ref "LED19") (pin "C") (pinfunction "C_C") (pintype "passive"))
      (node (ref "LED195") (pin "C") (pinfunction "C_C") (pintype "passive"))
      (node (ref "LED211") (pin "C") (pinfunction "C_C") (pintype "passive"))
      (node (ref "LED227") (pin "C") (pinfunction "C_C") (pintype "passive"))
      (node (ref "LED243") (pin "C") (pinfunction "C_C") (pintype "passive"))
      (node (ref "LED3") (pin "C") (pinfunction "C_C") (pintype "passive"))
      (node (ref "LED35") (pin "C") (pinfunction "C_C") (pintype "passive"))
      (node (ref "LED51") (pin "C") (pinfunction "C_C") (pintype "passive"))
      (node (ref "LED67") (pin "C") (pinfunction "C_C") (pintype "passive"))
      (node (ref "LED83") (pin "C") (pinfunction "C_C") (pintype "passive"))
      (node (ref "LED99") (pin "C") (pinfunction "C_C") (pintype "passive"))
      (node (ref "PAD3") (pin "1") (pinfunction "P_1") (pintype "passive"))
    )
    (net (code "4") (name "/X3") (class "Default")
      (node (ref "LED100") (pin "C") (pinfunction "C_C") (pintype "passive"))
      (node (ref "LED116") (pin "C") (pinfunction "C_C") (pintype "passive"))
      (node (ref "LED132") (pin "C") (pinfunction "C_C") (pintype "passive"))
      (node (ref "LED148") (pin "C") (pinfunction "C_C") (pintype "passive"))
      (node (ref "LED164") (pin "C") (pinfunction "C_C") (pintype "passive"))
      (node (ref "LED180") (pin "C") (pinfunction "C_C") (pintype "passive"))
      (node (ref "LED196") (pin "C") (pinfunction "C_C") (pintype "passive"))
      (node (ref "LED20") (pin "C") (pinfunction "C_C") (pintype "passive"))
      (node (ref "LED212") (pin "C") (pinfunction "C_C") (pintype "passive"))
      (node (ref "LED228") (pin "C") (pinfunction "C_C") (pintype "passive"))
      (node (ref "LED244") (pin "C") (pinfunction "C_C") (pintype "passive"))
      (node (ref "LED36") (pin "C") (pinfunction "C_C") (pintype "passive"))
      (node (ref "LED4") (pin "C") (pinfunction "C_C") (pintype "passive"))
      (node (ref "LED52") (pin "C") (pinfunction "C_C") (pintype "passive"))
      (node (ref "LED68") (pin "C") (pinfunction "C_C") (pintype "passive"))
      (node (ref "LED84") (pin "C") (pinfunction "C_C") (pintype "passive"))
      (node (ref "PAD4") (pin "1") (pinfunction "P_1") (pintype "passive"))
    )
    (net (code "5") (name "/X4") (class "Default")
      (node (ref "LED101") (pin "C") (pinfunction "C_C") (pintype "passive"))
      (node (ref "LED117") (pin "C") (pinfunction "C_C") (pintype "passive"))
      (node (ref "LED133") (pin "C") (pinfunction "C_C") (pintype "passive"))
      (node (ref "LED149") (pin "C") (pinfunction "C_C") (pintype "passive"))
      (node (ref "LED165") (pin "C") (pinfunction "C_C") (pintype "passive"))
      (node (ref "LED181") (pin "C") (pinfunction "C_C") (pintype "passive"))
      (node (ref "LED197") (pin "C") (pinfunction "C_C") (pintype "passive"))
      (node (ref "LED21") (pin "C") (pinfunction "C_C") (pintype "passive"))
      (node (ref "LED213") (pin "C") (pinfunction "C_C") (pintype "passive"))
      (node (ref "LED229") (pin "C") (pinfunction "C_C") (pintype "passive"))
      (node (ref "LED245") (pin "C") (pinfunction "C_C") (pintype "passive"))
      (node (ref "LED37") (pin "C") (pinfunction "C_C") (pintype "passive"))
      (node (ref "LED5") (pin "C") (pinfunction "C_C") (pintype "passive"))
      (node (ref "LED53") (pin "C") (pinfunction "C_C") (pintype "passive"))
      (node (ref "LED69") (pin "C") (pinfunction "C_C") (pintype "passive"))
      (node (ref "LED85") (pin "C") (pinfunction "C_C") (pintype "passive"))
      (node (ref "PAD5") (pin "1") (pinfunction "P_1") (pintype "passive"))
    )
    (net (code "6") (name "/X5") (class "Default")
      (node (ref "LED102") (pin "C") (pinfunction "C_C") (pintype "passive"))
      (node (ref "LED118") (pin "C") (pinfunction "C_C") (pintype "passive"))
      (node (ref "LED134") (pin "C") (pinfunction "C_C") (pintype "passive"))
      (node (ref "LED150") (pin "C") (pinfunction "C_C") (pintype "passive"))
      (node (ref "LED166") (pin "C") (pinfunction "C_C") (pintype "passive"))
      (node (ref "LED182") (pin "C") (pinfunction "C_C") (pintype "passive"))
      (node (ref "LED198") (pin "C") (pinfunction "C_C") (pintype "passive"))
      (node (ref "LED214") (pin "C") (pinfunction "C_C") (pintype "passive"))
      (node (ref "LED22") (pin "C") (pinfunction "C_C") (pintype "passive"))
      (node (ref "LED230") (pin "C") (pinfunction "C_C") (pintype "passive"))
      (node (ref "LED246") (pin "C") (pinfunction "C_C") (pintype "passive"))
      (node (ref "LED38") (pin "C") (pinfunction "C_C") (pintype "passive"))
      (node (ref "LED54") (pin "C") (pinfunction "C_C") (pintype "passive"))
      (node (ref "LED6") (pin "C") (pinfunction "C_C") (pintype "passive"))
      (node (ref "LED70") (pin "C") (pinfunction "C_C") (pintype "passive"))
      (node (ref "LED86") (pin "C") (pinfunction "C_C") (pintype "passive"))
      (node (ref "PAD6") (pin "1") (pinfunction "P_1") (pintype "passive"))
    )
    (net (code "7") (name "/X6") (class "Default")
      (node (ref "LED103") (pin "C") (pinfunction "C_C") (pintype "passive"))
      (node (ref "LED119") (pin "C") (pinfunction "C_C") (pintype "passive"))
      (node (ref "LED135") (pin "C") (pinfunction "C_C") (pintype "passive"))
      (node (ref "LED151") (pin "C") (pinfunction "C_C") (pintype "passive"))
      (node (ref "LED167") (pin "C") (pinfunction "C_C") (pintype "passive"))
      (node (ref "LED183") (pin "C") (pinfunction "C_C") (pintype "passive"))
      (node (ref "LED199") (pin "C") (pinfunction "C_C") (pintype "passive"))
      (node (ref "LED215") (pin "C") (pinfunction "C_C") (pintype "passive"))
      (node (ref "LED23") (pin "C") (pinfunction "C_C") (pintype "passive"))
      (node (ref "LED231") (pin "C") (pinfunction "C_C") (pintype "passive"))
      (node (ref "LED247") (pin "C") (pinfunction "C_C") (pintype "passive"))
      (node (ref "LED39") (pin "C") (pinfunction "C_C") (pintype "passive"))
      (node (ref "LED55") (pin "C") (pinfunction "C_C") (pintype "passive"))
      (node (ref "LED7") (pin "C") (pinfunction "C_C") (pintype "passive"))
      (node (ref "LED71") (pin "C") (pinfunction "C_C") (pintype "passive"))
      (node (ref "LED87") (pin "C") (pinfunction "C_C") (pintype "passive"))
      (node (ref "PAD7") (pin "1") (pinfunction "P_1") (pintype "passive"))
    )
    (net (code "8") (name "/X7") (class "Default")
      (node (ref "LED104") (pin "C") (pinfunction "C_C") (pintype "passive"))
      (node (ref "LED120") (pin "C") (pinfunction "C_C") (pintype "passive"))
      (node (ref "LED136") (pin "C") (pinfunction "C_C") (pintype "passive"))
      (node (ref "LED152") (pin "C") (pinfunction "C_C") (pintype "passive"))
      (node (ref "LED168") (pin "C") (pinfunction "C_C") (pintype "passive"))
      (node (ref "LED184") (pin "C") (pinfunction "C_C") (pintype "passive"))
      (node (ref "LED200") (pin "C") (pinfunction "C_C") (pintype "passive"))
      (node (ref "LED216") (pin "C") (pinfunction "C_C") (pintype "passive"))
      (node (ref "LED232") (pin "C") (pinfunction "C_C") (pintype "passive"))
      (node (ref "LED24") (pin "C") (pinfunction "C_C") (pintype "passive"))
      (node (ref "LED248") (pin "C") (pinfunction "C_C") (pintype "passive"))
      (node (ref "LED40") (pin "C") (pinfunction "C_C") (pintype "passive"))
      (node (ref "LED56") (pin "C") (pinfunction "C_C") (pintype "passive"))
      (node (ref "LED72") (pin "C") (pinfunction "C_C") (pintype "passive"))
      (node (ref "LED8") (pin "C") (pinfunction "C_C") (pintype "passive"))
      (node (ref "LED88") (pin "C") (pinfunction "C_C") (pintype "passive"))
      (node (ref "PAD8") (pin "1") (pinfunction "P_1") (pintype "passive"))
    )
    (net (code "9") (name "/X8") (class "Default")
      (node (ref "LED105") (pin "C") (pinfunction "C_C") (pintype "passive"))
      (node (ref "LED121") (pin "C") (pinfunction "C_C") (pintype "passive"))
      (node (ref "LED137") (pin "C") (pinfunction "C_C") (pintype "passive"))
      (node (ref "LED153") (pin "C") (pinfunction "C_C") (pintype "passive"))
      (node (ref "LED169") (pin "C") (pinfunction "C_C") (pintype "passive"))
      (node (ref "LED185") (pin "C") (pinfunction "C_C") (pintype "passive"))
      (node (ref "LED201") (pin "C") (pinfunction "C_C") (pintype "passive"))
      (node (ref "LED217") (pin "C") (pinfunction "C_C") (pintype "passive"))
      (node (ref "LED233") (pin "C") (pinfunction "C_C") (pintype "passive"))
      (node (ref "LED249") (pin "C") (pinfunction "C_C") (pintype "passive"))
      (node (ref "LED25") (pin "C") (pinfunction "C_C") (pintype "passive"))
      (node (ref "LED41") (pin "C") (pinfunction "C_C") (pintype "passive"))
      (node (ref "LED57") (pin "C") (pinfunction "C_C") (pintype "passive"))
      (node (ref "LED73") (pin "C") (pinfunction "C_C") (pintype "passive"))
      (node (ref "LED89") (pin "C") (pinfunction "C_C") (pintype "passive"))
      (node (ref "LED9") (pin "C") (pinfunction "C_C") (pintype "passive"))
      (node (ref "PAD9") (pin "1") (pinfunction "P_1") (pintype "passive"))
    )
    (net (code "10") (name "/X9") (class "Default")
      (node (ref "LED10") (pin "C") (pinfunction "C_C") (pintype "passive"))
      (node (ref "LED106") (pin "C") (pinfunction "C_C") (pintype "passive"))
      (node (ref "LED122") (pin "C") (pinfunction "C_C") (pintype "passive"))
      (node (ref "LED138") (pin "C") (pinfunction "C_C") (pintype "passive"))
      (node (ref "LED154") (pin "C") (pinfunction "C_C") (pintype "passive"))
      (node (ref "LED170") (pin "C") (pinfunction "C_C") (pintype "passive"))
      (node (ref "LED186") (pin "C") (pinfunction "C_C") (pintype "passive"))
      (node (ref "LED202") (pin "C") (pinfunction "C_C") (pintype "passive"))
      (node (ref "LED218") (pin "C") (pinfunction "C_C") (pintype "passive"))
      (node (ref "LED234") (pin "C") (pinfunction "C_C") (pintype "passive"))
      (node (ref "LED250") (pin "C") (pinfunction "C_C") (pintype "passive"))
      (node (ref "LED26") (pin "C") (pinfunction "C_C") (pintype "passive"))
      (node (ref "LED42") (pin "C") (pinfunction "C_C") (pintype "passive"))
      (node (ref "LED58") (pin "C") (pinfunction "C_C") (pintype "passive"))
      (node (ref "LED74") (pin "C") (pinfunction "C_C") (pintype "passive"))
      (node (ref "LED90") (pin "C") (pinfunction "C_C") (pintype "passive"))
      (node (ref "PAD10") (pin "1") (pinfunction "P_1") (pintype "passive"))
    )
    (net (code "11") (name "/X10") (class "Default")
      (node (ref "LED107") (pin "C") (pinfunction "C_C") (pintype "passive"))
      (node (ref "LED11") (pin "C") (pinfunction "C_C") (pintype "passive"))
      (node (ref "LED123") (pin "C") (pinfunction "C_C") (pintype "passive"))
      (node (ref "LED139") (pin "C") (pinfunction "C_C") (pintype "passive"))
      (node (ref "LED155") (pin "C") (pinfunction "C_C") (pintype "passive"))
      (node (ref "LED171") (pin "C") (pinfunction "C_C") (pintype "passive"))
      (node (ref "LED187") (pin "C") (pinfunction "C_C") (pintype "passive"))
      (node (ref "LED203") (pin "C") (pinfunction "C_C") (pintype "passive"))
      (node (ref "LED219") (pin "C") (pinfunction "C_C") (pintype "passive"))
      (node (ref "LED235") (pin "C") (pinfunction "C_C") (pintype "passive"))
      (node (ref "LED251") (pin "C") (pinfunction "C_C") (pintype "passive"))
      (node (ref "LED27") (pin "C") (pinfunction "C_C") (pintype "passive"))
      (node (ref "LED43") (pin "C") (pinfunction "C_C") (pintype "passive"))
      (node (ref "LED59") (pin "C") (pinfunction "C_C") (pintype "passive"))
      (node (ref "LED75") (pin "C") (pinfunction "C_C") (pintype "passive"))
      (node (ref "LED91") (pin "C") (pinfunction "C_C") (pintype "passive"))
      (node (ref "PAD11") (pin "1") (pinfunction "P_1") (pintype "passive"))
    )
    (net (code "12") (name "/X11") (class "Default")
      (node (ref "LED108") (pin "C") (pinfunction "C_C") (pintype "passive"))
      (node (ref "LED12") (pin "C") (pinfunction "C_C") (pintype "passive"))
      (node (ref "LED124") (pin "C") (pinfunction "C_C") (pintype "passive"))
      (node (ref "LED140") (pin "C") (pinfunction "C_C") (pintype "passive"))
      (node (ref "LED156") (pin "C") (pinfunction "C_C") (pintype "passive"))
      (node (ref "LED172") (pin "C") (pinfunction "C_C") (pintype "passive"))
      (node (ref "LED188") (pin "C") (pinfunction "C_C") (pintype "passive"))
      (node (ref "LED204") (pin "C") (pinfunction "C_C") (pintype "passive"))
      (node (ref "LED220") (pin "C") (pinfunction "C_C") (pintype "passive"))
      (node (ref "LED236") (pin "C") (pinfunction "C_C") (pintype "passive"))
      (node (ref "LED252") (pin "C") (pinfunction "C_C") (pintype "passive"))
      (node (ref "LED28") (pin "C") (pinfunction "C_C") (pintype "passive"))
      (node (ref "LED44") (pin "C") (pinfunction "C_C") (pintype "passive"))
      (node (ref "LED60") (pin "C") (pinfunction "C_C") (pintype "passive"))
      (node (ref "LED76") (pin "C") (pinfunction "C_C") (pintype "passive"))
      (node (ref "LED92") (pin "C") (pinfunction "C_C") (pintype "passive"))
      (node (ref "PAD12") (pin "1") (pinfunction "P_1") (pintype "passive"))
    )
    (net (code "13") (name "/X12") (class "Default")
      (node (ref "LED109") (pin "C") (pinfunction "C_C") (pintype "passive"))
      (node (ref "LED125") (pin "C") (pinfunction "C_C") (pintype "passive"))
      (node (ref "LED13") (pin "C") (pinfunction "C_C") (pintype "passive"))
      (node (ref "LED141") (pin "C") (pinfunction "C_C") (pintype "passive"))
      (node (ref "LED157") (pin "C") (pinfunction "C_C") (pintype "passive"))
      (node (ref "LED173") (pin "C") (pinfunction "C_C") (pintype "passive"))
      (node (ref "LED189") (pin "C") (pinfunction "C_C") (pintype "passive"))
      (node (ref "LED205") (pin "C") (pinfunction "C_C") (pintype "passive"))
      (node (ref "LED221") (pin "C") (pinfunction "C_C") (pintype "passive"))
      (node (ref "LED237") (pin "C") (pinfunction "C_C") (pintype "passive"))
      (node (ref "LED253") (pin "C") (pinfunction "C_C") (pintype "passive"))
      (node (ref "LED29") (pin "C") (pinfunction "C_C") (pintype "passive"))
      (node (ref "LED45") (pin "C") (pinfunction "C_C") (pintype "passive"))
      (node (ref "LED61") (pin "C") (pinfunction "C_C") (pintype "passive"))
      (node (ref "LED77") (pin "C") (pinfunction "C_C") (pintype "passive"))
      (node (ref "LED93") (pin "C") (pinfunction "C_C") (pintype "passive"))
      (node (ref "PAD13") (pin "1") (pinfunction "P_1") (pintype "passive"))
    )
    (net (code "14") (name "/X13") (class "Default")
      (node (ref "LED110") (pin "C") (pinfunction "C_C") (pintype "passive"))
      (node (ref "LED126") (pin "C") (pinfunction "C_C") (pintype "passive"))
      (node (ref "LED14") (pin "C") (pinfunction "C_C") (pintype "passive"))
      (node (ref "LED142") (pin "C") (pinfunction "C_C") (pintype "passive"))
      (node (ref "LED158") (pin "C") (pinfunction "C_C") (pintype "passive"))
      (node (ref "LED174") (pin "C") (pinfunction "C_C") (pintype "passive"))
      (node (ref "LED190") (pin "C") (pinfunction "C_C") (pintype "passive"))
      (node (ref "LED206") (pin "C") (pinfunction "C_C") (pintype "passive"))
      (node (ref "LED222") (pin "C") (pinfunction "C_C") (pintype "passive"))
      (node (ref "LED238") (pin "C") (pinfunction "C_C") (pintype "passive"))
      (node (ref "LED254") (pin "C") (pinfunction "C_C") (pintype "passive"))
      (node (ref "LED30") (pin "C") (pinfunction "C_C") (pintype "passive"))
      (node (ref "LED46") (pin "C") (pinfunction "C_C") (pintype "passive"))
      (node (ref "LED62") (pin "C") (pinfunction "C_C") (pintype "passive"))
      (node (ref "LED78") (pin "C") (pinfunction "C_C") (pintype "passive"))
      (node (ref "LED94") (pin "C") (pinfunction "C_C") (pintype "passive"))
      (node (ref "PAD14") (pin "1") (pinfunction "P_1") (pintype "passive"))
    )
    (net (code "15") (name "/X14") (class "Default")
      (node (ref "LED111") (pin "C") (pinfunction "C_C") (pintype "passive"))
      (node (ref "LED127") (pin "C") (pinfunction "C_C") (pintype "passive"))
      (node (ref "LED143") (pin "C") (pinfunction "C_C") (pintype "passive"))
      (node (ref "LED15") (pin "C") (pinfunction "C_C") (pintype "passive"))
      (node (ref "LED159") (pin "C") (pinfunction "C_C") (pintype "passive"))
      (node (ref "LED175") (pin "C") (pinfunction "C_C") (pintype "passive"))
      (node (ref "LED191") (pin "C") (pinfunction "C_C") (pintype "passive"))
      (node (ref "LED207") (pin "C") (pinfunction "C_C") (pintype "passive"))
      (node (ref "LED223") (pin "C") (pinfunction "C_C") (pintype "passive"))
      (node (ref "LED239") (pin "C") (pinfunction "C_C") (pintype "passive"))
      (node (ref "LED255") (pin "C") (pinfunction "C_C") (pintype "passive"))
      (node (ref "LED31") (pin "C") (pinfunction "C_C") (pintype "passive"))
      (node (ref "LED47") (pin "C") (pinfunction "C_C") (pintype "passive"))
      (node (ref "LED63") (pin "C") (pinfunction "C_C") (pintype "passive"))
      (node (ref "LED79") (pin "C") (pinfunction "C_C") (pintype "passive"))
      (node (ref "LED95") (pin "C") (pinfunction "C_C") (pintype "passive"))
      (node (ref "PAD15") (pin "1") (pinfunction "P_1") (pintype "passive"))
    )
    (net (code "16") (name "/X15") (class "Default")
      (node (ref "LED112") (pin "C") (pinfunction "C_C") (pintype "passive"))
      (node (ref "LED128") (pin "C") (pinfunction "C_C") (pintype "passive"))
      (node (ref "LED144") (pin "C") (pinfunction "C_C") (pintype "passive"))
      (node (ref "LED16") (pin "C") (pinfunction "C_C") (pintype "passive"))
      (node (ref "LED160") (pin "C") (pinfunction "C_C") (pintype "passive"))
      (node (ref "LED176") (pin "C") (pinfunction "C_C") (pintype "passive"))
      (node (ref "LED192") (pin "C") (pinfunction "C_C") (pintype "passive"))
      (node (ref "LED208") (pin "C") (pinfunction "C_C") (pintype "passive"))
      (node (ref "LED224") (pin "C") (pinfunction "C_C") (pintype "passive"))
      (node (ref "LED240") (pin "C") (pinfunction "C_C") (pintype "passive"))
      (node (ref "LED256") (pin "C") (pinfunction "C_C") (pintype "passive"))
      (node (ref "LED32") (pin "C") (pinfunction "C_C") (pintype "passive"))
      (node (ref "LED48") (pin "C") (pinfunction "C_C") (pintype "passive"))
      (node (ref "LED64") (pin "C") (pinfunction "C_C") (pintype "passive"))
      (node (ref "LED80") (pin "C") (pinfunction "C_C") (pintype "passive"))
      (node (ref "LED96") (pin "C") (pinfunction "C_C") (pintype "passive"))
      (node (ref "PAD16") (pin "1") (pinfunction "P_1") (pintype "passive"))
    )
    (net (code "17") (name "/Y0") (class "Default")
      (node (ref "LED1") (pin "A") (pinfunction "A_A") (pintype "passive"))
      (node (ref "LED10") (pin "A") (pinfunction "A_A") (pintype "passive"))
      (node (ref "LED11") (pin "A") (pinfunction "A_A") (pintype "passive"))
      (node (ref "LED12") (pin "A") (pinfunction "A_A") (pintype "passive"))
      (node (ref "LED13") (pin "A") (pinfunction "A_A") (pintype "passive"))
      (node (ref "LED14") (pin "A") (pinfunction "A_A") (pintype "passive"))
      (node (ref "LED15") (pin "A") (pinfunction "A_A") (pintype "passive"))
      (node (ref "LED16") (pin "A") (pinfunction "A_A") (pintype "passive"))
      (node (ref "LED2") (pin "A") (pinfunction "A_A") (pintype "passive"))
      (node (ref "LED3") (pin "A") (pinfunction "A_A") (pintype "passive"))
      (node (ref "LED4") (pin "A") (pinfunction "A_A") (pintype "passive"))
      (node (ref "LED5") (pin "A") (pinfunction "A_A") (pintype "passive"))
      (node (ref "LED6") (pin "A") (pinfunction "A_A") (pintype "passive"))
      (node (ref "LED7") (pin "A") (pinfunction "A_A") (pintype "passive"))
      (node (ref "LED8") (pin "A") (pinfunction "A_A") (pintype "passive"))
      (node (ref "LED9") (pin "A") (pinfunction "A_A") (pintype "passive"))
      (node (ref "PAD17") (pin "1") (pinfunction "P_1") (pintype "passive"))
    )
    (net (code "18") (name "/Y1") (class "Default")
      (node (ref "LED17") (pin "A") (pinfunction "A_A") (pintype "passive"))
      (node (ref "LED18") (pin "A") (pinfunction "A_A") (pintype "passive"))
      (node (ref "LED19") (pin "A") (pinfunction "A_A") (pintype "passive"))
      (node (ref "LED20") (pin "A") (pinfunction "A_A") (pintype "passive"))
      (node (ref "LED21") (pin "A") (pinfunction "A_A") (pintype "passive"))
      (node (ref "LED22") (pin "A") (pinfunction "A_A") (pintype "passive"))
      (node (ref "LED23") (pin "A") (pinfunction "A_A") (pintype "passive"))
      (node (ref "LED24") (pin "A") (pinfunction "A_A") (pintype "passive"))
      (node (ref "LED25") (pin "A") (pinfunction "A_A") (pintype "passive"))
      (node (ref "LED26") (pin "A") (pinfunction "A_A") (pintype "passive"))
      (node (ref "LED27") (pin "A") (pinfunction "A_A") (pintype "passive"))
      (node (ref "LED28") (pin "A") (pinfunction "A_A") (pintype "passive"))
      (node (ref "LED29") (pin "A") (pinfunction "A_A") (pintype "passive"))
      (node (ref "LED30") (pin "A") (pinfunction "A_A") (pintype "passive"))
      (node (ref "LED31") (pin "A") (pinfunction "A_A") (pintype "passive"))
      (node (ref "LED32") (pin "A") (pinfunction "A_A") (pintype "passive"))
      (node (ref "PAD18") (pin "1") (pinfunction "P_1") (pintype "passive"))
    )
    (net (code "19") (name "/Y2") (class "Default")
      (node (ref "LED33") (pin "A") (pinfunction "A_A") (pintype "passive"))
      (node (ref "LED34") (pin "A") (pinfunction "A_A") (pintype "passive"))
      (node (ref "LED35") (pin "A") (pinfunction "A_A") (pintype "passive"))
      (node (ref "LED36") (pin "A") (pinfunction "A_A") (pintype "passive"))
      (node (ref "LED37") (pin "A") (pinfunction "A_A") (pintype "passive"))
      (node (ref "LED38") (pin "A") (pinfunction "A_A") (pintype "passive"))
      (node (ref "LED39") (pin "A") (pinfunction "A_A") (pintype "passive"))
      (node (ref "LED40") (pin "A") (pinfunction "A_A") (pintype "passive"))
      (node (ref "LED41") (pin "A") (pinfunction "A_A") (pintype "passive"))
      (node (ref "LED42") (pin "A") (pinfunction "A_A") (pintype "passive"))
      (node (ref "LED43") (pin "A") (pinfunction "A_A") (pintype "passive"))
      (node (ref "LED44") (pin "A") (pinfunction "A_A") (pintype "passive"))
      (node (ref "LED45") (pin "A") (pinfunction "A_A") (pintype "passive"))
      (node (ref "LED46") (pin "A") (pinfunction "A_A") (pintype "passive"))
      (node (ref "LED47") (pin "A") (pinfunction "A_A") (pintype "passive"))
      (node (ref "LED48") (pin "A") (pinfunction "A_A") (pintype "passive"))
      (node (ref "PAD19") (pin "1") (pinfunction "P_1") (pintype "passive"))
    )
    (net (code "20") (name "/Y3") (class "Default")
      (node (ref "LED49") (pin "A") (pinfunction "A_A") (pintype "passive"))
      (node (ref "LED50") (pin "A") (pinfunction "A_A") (pintype "passive"))
      (node (ref "LED51") (pin "A") (pinfunction "A_A") (pintype "passive"))
      (node (ref "LED52") (pin "A") (pinfunction "A_A") (pintype "passive"))
      (node (ref "LED53") (pin "A") (pinfunction "A_A") (pintype "passive"))
      (node (ref "LED54") (pin "A") (pinfunction "A_A") (pintype "passive"))
      (node (ref "LED55") (pin "A") (pinfunction "A_A") (pintype "passive"))
      (node (ref "LED56") (pin "A") (pinfunction "A_A") (pintype "passive"))
      (node (ref "LED57") (pin "A") (pinfunction "A_A") (pintype "passive"))
      (node (ref "LED58") (pin "A") (pinfunction "A_A") (pintype "passive"))
      (node (ref "LED59") (pin "A") (pinfunction "A_A") (pintype "passive"))
      (node (ref "LED60") (pin "A") (pinfunction "A_A") (pintype "passive"))
      (node (ref "LED61") (pin "A") (pinfunction "A_A") (pintype "passive"))
      (node (ref "LED62") (pin "A") (pinfunction "A_A") (pintype "passive"))
      (node (ref "LED63") (pin "A") (pinfunction "A_A") (pintype "passive"))
      (node (ref "LED64") (pin "A") (pinfunction "A_A") (pintype "passive"))
      (node (ref "PAD20") (pin "1") (pinfunction "P_1") (pintype "passive"))
    )
    (net (code "21") (name "/Y4") (class "Default")
      (node (ref "LED65") (pin "A") (pinfunction "A_A") (pintype "passive"))
      (node (ref "LED66") (pin "A") (pinfunction "A_A") (pintype "passive"))
      (node (ref "LED67") (pin "A") (pinfunction "A_A") (pintype "passive"))
      (node (ref "LED68") (pin "A") (pinfunction "A_A") (pintype "passive"))
      (node (ref "LED69") (pin "A") (pinfunction "A_A") (pintype "passive"))
      (node (ref "LED70") (pin "A") (pinfunction "A_A") (pintype "passive"))
      (node (ref "LED71") (pin "A") (pinfunction "A_A") (pintype "passive"))
      (node (ref "LED72") (pin "A") (pinfunction "A_A") (pintype "passive"))
      (node (ref "LED73") (pin "A") (pinfunction "A_A") (pintype "passive"))
      (node (ref "LED74") (pin "A") (pinfunction "A_A") (pintype "passive"))
      (node (ref "LED75") (pin "A") (pinfunction "A_A") (pintype "passive"))
      (node (ref "LED76") (pin "A") (pinfunction "A_A") (pintype "passive"))
      (node (ref "LED77") (pin "A") (pinfunction "A_A") (pintype "passive"))
      (node (ref "LED78") (pin "A") (pinfunction "A_A") (pintype "passive"))
      (node (ref "LED79") (pin "A") (pinfunction "A_A") (pintype "passive"))
      (node (ref "LED80") (pin "A") (pinfunction "A_A") (pintype "passive"))
      (node (ref "PAD21") (pin "1") (pinfunction "P_1") (pintype "passive"))
    )
    (net (code "22") (name "/Y5") (class "Default")
      (node (ref "LED81") (pin "A") (pinfunction "A_A") (pintype "passive"))
      (node (ref "LED82") (pin "A") (pinfunction "A_A") (pintype "passive"))
      (node (ref "LED83") (pin "A") (pinfunction "A_A") (pintype "passive"))
      (node (ref "LED84") (pin "A") (pinfunction "A_A") (pintype "passive"))
      (node (ref "LED85") (pin "A") (pinfunction "A_A") (pintype "passive"))
      (node (ref "LED86") (pin "A") (pinfunction "A_A") (pintype "passive"))
      (node (ref "LED87") (pin "A") (pinfunction "A_A") (pintype "passive"))
      (node (ref "LED88") (pin "A") (pinfunction "A_A") (pintype "passive"))
      (node (ref "LED89") (pin "A") (pinfunction "A_A") (pintype "passive"))
      (node (ref "LED90") (pin "A") (pinfunction "A_A") (pintype "passive"))
      (node (ref "LED91") (pin "A") (pinfunction "A_A") (pintype "passive"))
      (node (ref "LED92") (pin "A") (pinfunction "A_A") (pintype "passive"))
      (node (ref "LED93") (pin "A") (pinfunction "A_A") (pintype "passive"))
      (node (ref "LED94") (pin "A") (pinfunction "A_A") (pintype "passive"))
      (node (ref "LED95") (pin "A") (pinfunction "A_A") (pintype "passive"))
      (node (ref "LED96") (pin "A") (pinfunction "A_A") (pintype "passive"))
      (node (ref "PAD22") (pin "1") (pinfunction "P_1") (pintype "passive"))
    )
    (net (code "23") (name "/Y6") (class "Default")
      (node (ref "LED100") (pin "A") (pinfunction "A_A") (pintype "passive"))
      (node (ref "LED101") (pin "A") (pinfunction "A_A") (pintype "passive"))
      (node (ref "LED102") (pin "A") (pinfunction "A_A") (pintype "passive"))
      (node (ref "LED103") (pin "A") (pinfunction "A_A") (pintype "passive"))
      (node (ref "LED104") (pin "A") (pinfunction "A_A") (pintype "passive"))
      (node (ref "LED105") (pin "A") (pinfunction "A_A") (pintype "passive"))
      (node (ref "LED106") (pin "A") (pinfunction "A_A") (pintype "passive"))
      (node (ref "LED107") (pin "A") (pinfunction "A_A") (pintype "passive"))
      (node (ref "LED108") (pin "A") (pinfunction "A_A") (pintype "passive"))
      (node (ref "LED109") (pin "A") (pinfunction "A_A") (pintype "passive"))
      (node (ref "LED110") (pin "A") (pinfunction "A_A") (pintype "passive"))
      (node (ref "LED111") (pin "A") (pinfunction "A_A") (pintype "passive"))
      (node (ref "LED112") (pin "A") (pinfunction "A_A") (pintype "passive"))
      (node (ref "LED97") (pin "A") (pinfunction "A_A") (pintype "passive"))
      (node (ref "LED98") (pin "A") (pinfunction "A_A") (pintype "passive"))
      (node (ref "LED99") (pin "A") (pinfunction "A_A") (pintype "passive"))
      (node (ref "PAD23") (pin "1") (pinfunction "P_1") (pintype "passive"))
    )
    (net (code "24") (name "/Y7") (class "Default")
      (node (ref "LED113") (pin "A") (pinfunction "A_A") (pintype "passive"))
      (node (ref "LED114") (pin "A") (pinfunction "A_A") (pintype "passive"))
      (node (ref "LED115") (pin "A") (pinfunction "A_A") (pintype "passive"))
      (node (ref "LED116") (pin "A") (pinfunction "A_A") (pintype "passive"))
      (node (ref "LED117") (pin "A") (pinfunction "A_A") (pintype "passive"))
      (node (ref "LED118") (pin "A") (pinfunction "A_A") (pintype "passive"))
      (node (ref "LED119") (pin "A") (pinfunction "A_A") (pintype "passive"))
      (node (ref "LED120") (pin "A") (pinfunction "A_A") (pintype "passive"))
      (node (ref "LED121") (pin "A") (pinfunction "A_A") (pintype "passive"))
      (node (ref "LED122") (pin "A") (pinfunction "A_A") (pintype "passive"))
      (node (ref "LED123") (pin "A") (pinfunction "A_A") (pintype "passive"))
      (node (ref "LED124") (pin "A") (pinfunction "A_A") (pintype "passive"))
      (node (ref "LED125") (pin "A") (pinfunction "A_A") (pintype "passive"))
      (node (ref "LED126") (pin "A") (pinfunction "A_A") (pintype "passive"))
      (node (ref "LED127") (pin "A") (pinfunction "A_A") (pintype "passive"))
      (node (ref "LED128") (pin "A") (pinfunction "A_A") (pintype "passive"))
      (node (ref "PAD24") (pin "1") (pinfunction "P_1") (pintype "passive"))
    )
    (net (code "25") (name "/Y8") (class "Default")
      (node (ref "LED129") (pin "A") (pinfunction "A_A") (pintype "passive"))
      (node (ref "LED130") (pin "A") (pinfunction "A_A") (pintype "passive"))
      (node (ref "LED131") (pin "A") (pinfunction "A_A") (pintype "passive"))
      (node (ref "LED132") (pin "A") (pinfunction "A_A") (pintype "passive"))
      (node (ref "LED133") (pin "A") (pinfunction "A_A") (pintype "passive"))
      (node (ref "LED134") (pin "A") (pinfunction "A_A") (pintype "passive"))
      (node (ref "LED135") (pin "A") (pinfunction "A_A") (pintype "passive"))
      (node (ref "LED136") (pin "A") (pinfunction "A_A") (pintype "passive"))
      (node (ref "LED137") (pin "A") (pinfunction "A_A") (pintype "passive"))
      (node (ref "LED138") (pin "A") (pinfunction "A_A") (pintype "passive"))
      (node (ref "LED139") (pin "A") (pinfunction "A_A") (pintype "passive"))
      (node (ref "LED140") (pin "A") (pinfunction "A_A") (pintype "passive"))
      (node (ref "LED141") (pin "A") (pinfunction "A_A") (pintype "passive"))
      (node (ref "LED142") (pin "A") (pinfunction "A_A") (pintype "passive"))
      (node (ref "LED143") (pin "A") (pinfunction "A_A") (pintype "passive"))
      (node (ref "LED144") (pin "A") (pinfunction "A_A") (pintype "passive"))
      (node (ref "PAD25") (pin "1") (pinfunction "P_1") (pintype "passive"))
    )
    (net (code "26") (name "/Y9") (class "Default")
      (node (ref "LED145") (pin "A") (pinfunction "A_A") (pintype "passive"))
      (node (ref "LED146") (pin "A") (pinfunction "A_A") (pintype "passive"))
      (node (ref "LED147") (pin "A") (pinfunction "A_A") (pintype "passive"))
      (node (ref "LED148") (pin "A") (pinfunction "A_A") (pintype "passive"))
      (node (ref "LED149") (pin "A") (pinfunction "A_A") (pintype "passive"))
      (node (ref "LED150") (pin "A") (pinfunction "A_A") (pintype "passive"))
      (node (ref "LED151") (pin "A") (pinfunction "A_A") (pintype "passive"))
      (node (ref "LED152") (pin "A") (pinfunction "A_A") (pintype "passive"))
      (node (ref "LED153") (pin "A") (pinfunction "A_A") (pintype "passive"))
      (node (ref "LED154") (pin "A") (pinfunction "A_A") (pintype "passive"))
      (node (ref "LED155") (pin "A") (pinfunction "A_A") (pintype "passive"))
      (node (ref "LED156") (pin "A") (pinfunction "A_A") (pintype "passive"))
      (node (ref "LED157") (pin "A") (pinfunction "A_A") (pintype "passive"))
      (node (ref "LED158") (pin "A") (pinfunction "A_A") (pintype "passive"))
      (node (ref "LED159") (pin "A") (pinfunction "A_A") (pintype "passive"))
      (node (ref "LED160") (pin "A") (pinfunction "A_A") (pintype "passive"))
      (node (ref "PAD26") (pin "1") (pinfunction "P_1") (pintype "passive"))
    )
    (net (code "27") (name "/Y10") (class "Default")
      (node (ref "LED161") (pin "A") (pinfunction "A_A") (pintype "passive"))
      (node (ref "LED162") (pin "A") (pinfunction "A_A") (pintype "passive"))
      (node (ref "LED163") (pin "A") (pinfunction "A_A") (pintype "passive"))
      (node (ref "LED164") (pin "A") (pinfunction "A_A") (pintype "passive"))
      (node (ref "LED165") (pin "A") (pinfunction "A_A") (pintype "passive"))
      (node (ref "LED166") (pin "A") (pinfunction "A_A") (pintype "passive"))
      (node (ref "LED167") (pin "A") (pinfunction "A_A") (pintype "passive"))
      (node (ref "LED168") (pin "A") (pinfunction "A_A") (pintype "passive"))
      (node (ref "LED169") (pin "A") (pinfunction "A_A") (pintype "passive"))
      (node (ref "LED170") (pin "A") (pinfunction "A_A") (pintype "passive"))
      (node (ref "LED171") (pin "A") (pinfunction "A_A") (pintype "passive"))
      (node (ref "LED172") (pin "A") (pinfunction "A_A") (pintype "passive"))
      (node (ref "LED173") (pin "A") (pinfunction "A_A") (pintype "passive"))
      (node (ref "LED174") (pin "A") (pinfunction "A_A") (pintype "passive"))
      (node (ref "LED175") (pin "A") (pinfunction "A_A") (pintype "passive"))
      (node (ref "LED176") (pin "A") (pinfunction "A_A") (pintype "passive"))
      (node (ref "PAD27") (pin "1") (pinfunction "P_1") (pintype "passive"))
    )
    (net (code "28") (name "/Y11") (class "Default")
      (node (ref "LED177") (pin "A") (pinfunction "A_A") (pintype "passive"))
      (node (ref "LED178") (pin "A") (pinfunction "A_A") (pintype "passive"))
      (node (ref "LED179") (pin "A") (pinfunction "A_A") (pintype "passive"))
      (node (ref "LED180") (pin "A") (pinfunction "A_A") (pintype "passive"))
      (node (ref "LED181") (pin "A") (pinfunction "A_A") (pintype "passive"))
      (node (ref "LED182") (pin "A") (pinfunction "A_A") (pintype "passive"))
      (node (ref "LED183") (pin "A") (pinfunction "A_A") (pintype "passive"))
      (node (ref "LED184") (pin "A") (pinfunction "A_A") (pintype "passive"))
      (node (ref "LED185") (pin "A") (pinfunction "A_A") (pintype "passive"))
      (node (ref "LED186") (pin "A") (pinfunction "A_A") (pintype "passive"))
      (node (ref "LED187") (pin "A") (pinfunction "A_A") (pintype "passive"))
      (node (ref "LED188") (pin "A") (pinfunction "A_A") (pintype "passive"))
      (node (ref "LED189") (pin "A") (pinfunction "A_A") (pintype "passive"))
      (node (ref "LED190") (pin "A") (pinfunction "A_A") (pintype "passive"))
      (node (ref "LED191") (pin "A") (pinfunction "A_A") (pintype "passive"))
      (node (ref "LED192") (pin "A") (pinfunction "A_A") (pintype "passive"))
      (node (ref "PAD28") (pin "1") (pinfunction "P_1") (pintype "passive"))
    )
    (net (code "29") (name "/Y12") (class "Default")
      (node (ref "LED193") (pin "A") (pinfunction "A_A") (pintype "passive"))
      (node (ref "LED194") (pin "A") (pinfunction "A_A") (pintype "passive"))
      (node (ref "LED195") (pin "A") (pinfunction "A_A") (pintype "passive"))
      (node (ref "LED196") (pin "A") (pinfunction "A_A") (pintype "passive"))
      (node (ref "LED197") (pin "A") (pinfunction "A_A") (pintype "passive"))
      (node (ref "LED198") (pin "A") (pinfunction "A_A") (pintype "passive"))
      (node (ref "LED199") (pin "A") (pinfunction "A_A") (pintype "passive"))
      (node (ref "LED200") (pin "A") (pinfunction "A_A") (pintype "passive"))
      (node (ref "LED201") (pin "A") (pinfunction "A_A") (pintype "passive"))
      (node (ref "LED202") (pin "A") (pinfunction "A_A") (pintype "passive"))
      (node (ref "LED203") (pin "A") (pinfunction "A_A") (pintype "passive"))
      (node (ref "LED204") (pin "A") (pinfunction "A_A") (pintype "passive"))
      (node (ref "LED205") (pin "A") (pinfunction "A_A") (pintype "passive"))
      (node (ref "LED206") (pin "A") (pinfunction "A_A") (pintype "passive"))
      (node (ref "LED207") (pin "A") (pinfunction "A_A") (pintype "passive"))
      (node (ref "LED208") (pin "A") (pinfunction "A_A") (pintype "passive"))
      (node (ref "PAD29") (pin "1") (pinfunction "P_1") (pintype "passive"))
    )
    (net (code "30") (name "/Y13") (class "Default")
      (node (ref "LED209") (pin "A") (pinfunction "A_A") (pintype "passive"))
      (node (ref "LED210") (pin "A") (pinfunction "A_A") (pintype "passive"))
      (node (ref "LED211") (pin "A") (pinfunction "A_A") (pintype "passive"))
      (node (ref "LED212") (pin "A") (pinfunction "A_A") (pintype "passive"))
      (node (ref "LED213") (pin "A") (pinfunction "A_A") (pintype "passive"))
      (node (ref "LED214") (pin "A") (pinfunction "A_A") (pintype "passive"))
      (node (ref "LED215") (pin "A") (pinfunction "A_A") (pintype "passive"))
      (node (ref "LED216") (pin "A") (pinfunction "A_A") (pintype "passive"))
      (node (ref "LED217") (pin "A") (pinfunction "A_A") (pintype "passive"))
      (node (ref "LED218") (pin "A") (pinfunction "A_A") (pintype "passive"))
      (node (ref "LED219") (pin "A") (pinfunction "A_A") (pintype "passive"))
      (node (ref "LED220") (pin "A") (pinfunction "A_A") (pintype "passive"))
      (node (ref "LED221") (pin "A") (pinfunction "A_A") (pintype "passive"))
      (node (ref "LED222") (pin "A") (pinfunction "A_A") (pintype "passive"))
      (node (ref "LED223") (pin "A") (pinfunction "A_A") (pintype "passive"))
      (node (ref "LED224") (pin "A") (pinfunction "A_A") (pintype "passive"))
      (node (ref "PAD30") (pin "1") (pinfunction "P_1") (pintype "passive"))
    )
    (net (code "31") (name "/Y14") (class "Default")
      (node (ref "LED225") (pin "A") (pinfunction "A_A") (pintype "passive"))
      (node (ref "LED226") (pin "A") (pinfunction "A_A") (pintype "passive"))
      (node (ref "LED227") (pin "A") (pinfunction "A_A") (pintype "passive"))
      (node (ref "LED228") (pin "A") (pinfunction "A_A") (pintype "passive"))
      (node (ref "LED229") (pin "A") (pinfunction "A_A") (pintype "passive"))
      (node (ref "LED230") (pin "A") (pinfunction "A_A") (pintype "passive"))
      (node (ref "LED231") (pin "A") (pinfunction "A_A") (pintype "passive"))
      (node (ref "LED232") (pin "A") (pinfunction "A_A") (pintype "passive"))
      (node (ref "LED233") (pin "A") (pinfunction "A_A") (pintype "passive"))
      (node (ref "LED234") (pin "A") (pinfunction "A_A") (pintype "passive"))
      (node (ref "LED235") (pin "A") (pinfunction "A_A") (pintype "passive"))
      (node (ref "LED236") (pin "A") (pinfunction "A_A") (pintype "passive"))
      (node (ref "LED237") (pin "A") (pinfunction "A_A") (pintype "passive"))
      (node (ref "LED238") (pin "A") (pinfunction "A_A") (pintype "passive"))
      (node (ref "LED239") (pin "A") (pinfunction "A_A") (pintype "passive"))
      (node (ref "LED240") (pin "A") (pinfunction "A_A") (pintype "passive"))
      (node (ref "PAD31") (pin "1") (pinfunction "P_1") (pintype "passive"))
    )
    (net (code "32") (name "/Y15") (class "Default")
      (node (ref "LED241") (pin "A") (pinfunction "A_A") (pintype "passive"))
      (node (ref "LED242") (pin "A") (pinfunction "A_A") (pintype "passive"))
      (node (ref "LED243") (pin "A") (pinfunction "A_A") (pintype "passive"))
      (node (ref "LED244") (pin "A") (pinfunction "A_A") (pintype "passive"))
      (node (ref "LED245") (pin "A") (pinfunction "A_A") (pintype "passive"))
      (node (ref "LED246") (pin "A") (pinfunction "A_A") (pintype "passive"))
      (node (ref "LED247") (pin "A") (pinfunction "A_A") (pintype "passive"))
      (node (ref "LED248") (pin "A") (pinfunction "A_A") (pintype "passive"))
      (node (ref "LED249") (pin "A") (pinfunction "A_A") (pintype "passive"))
      (node (ref "LED250") (pin "A") (pinfunction "A_A") (pintype "passive"))
      (node (ref "LED251") (pin "A") (pinfunction "A_A") (pintype "passive"))
      (node (ref "LED252") (pin "A") (pinfunction "A_A") (pintype "passive"))
      (node (ref "LED253") (pin "A") (pinfunction "A_A") (pintype "passive"))
      (node (ref "LED254") (pin "A") (pinfunction "A_A") (pintype "passive"))
      (node (ref "LED255") (pin "A") (pinfunction "A_A") (pintype "passive"))
      (node (ref "LED256") (pin "A") (pinfunction "A_A") (pintype "passive"))
      (node (ref "PAD32") (pin "1") (pinfunction "P_1") (pintype "passive"))
    )
  )
)
